# QUTMS_CMU_type2_1_1.net
KiCad netlist of a schematic drawn in Altium Designer
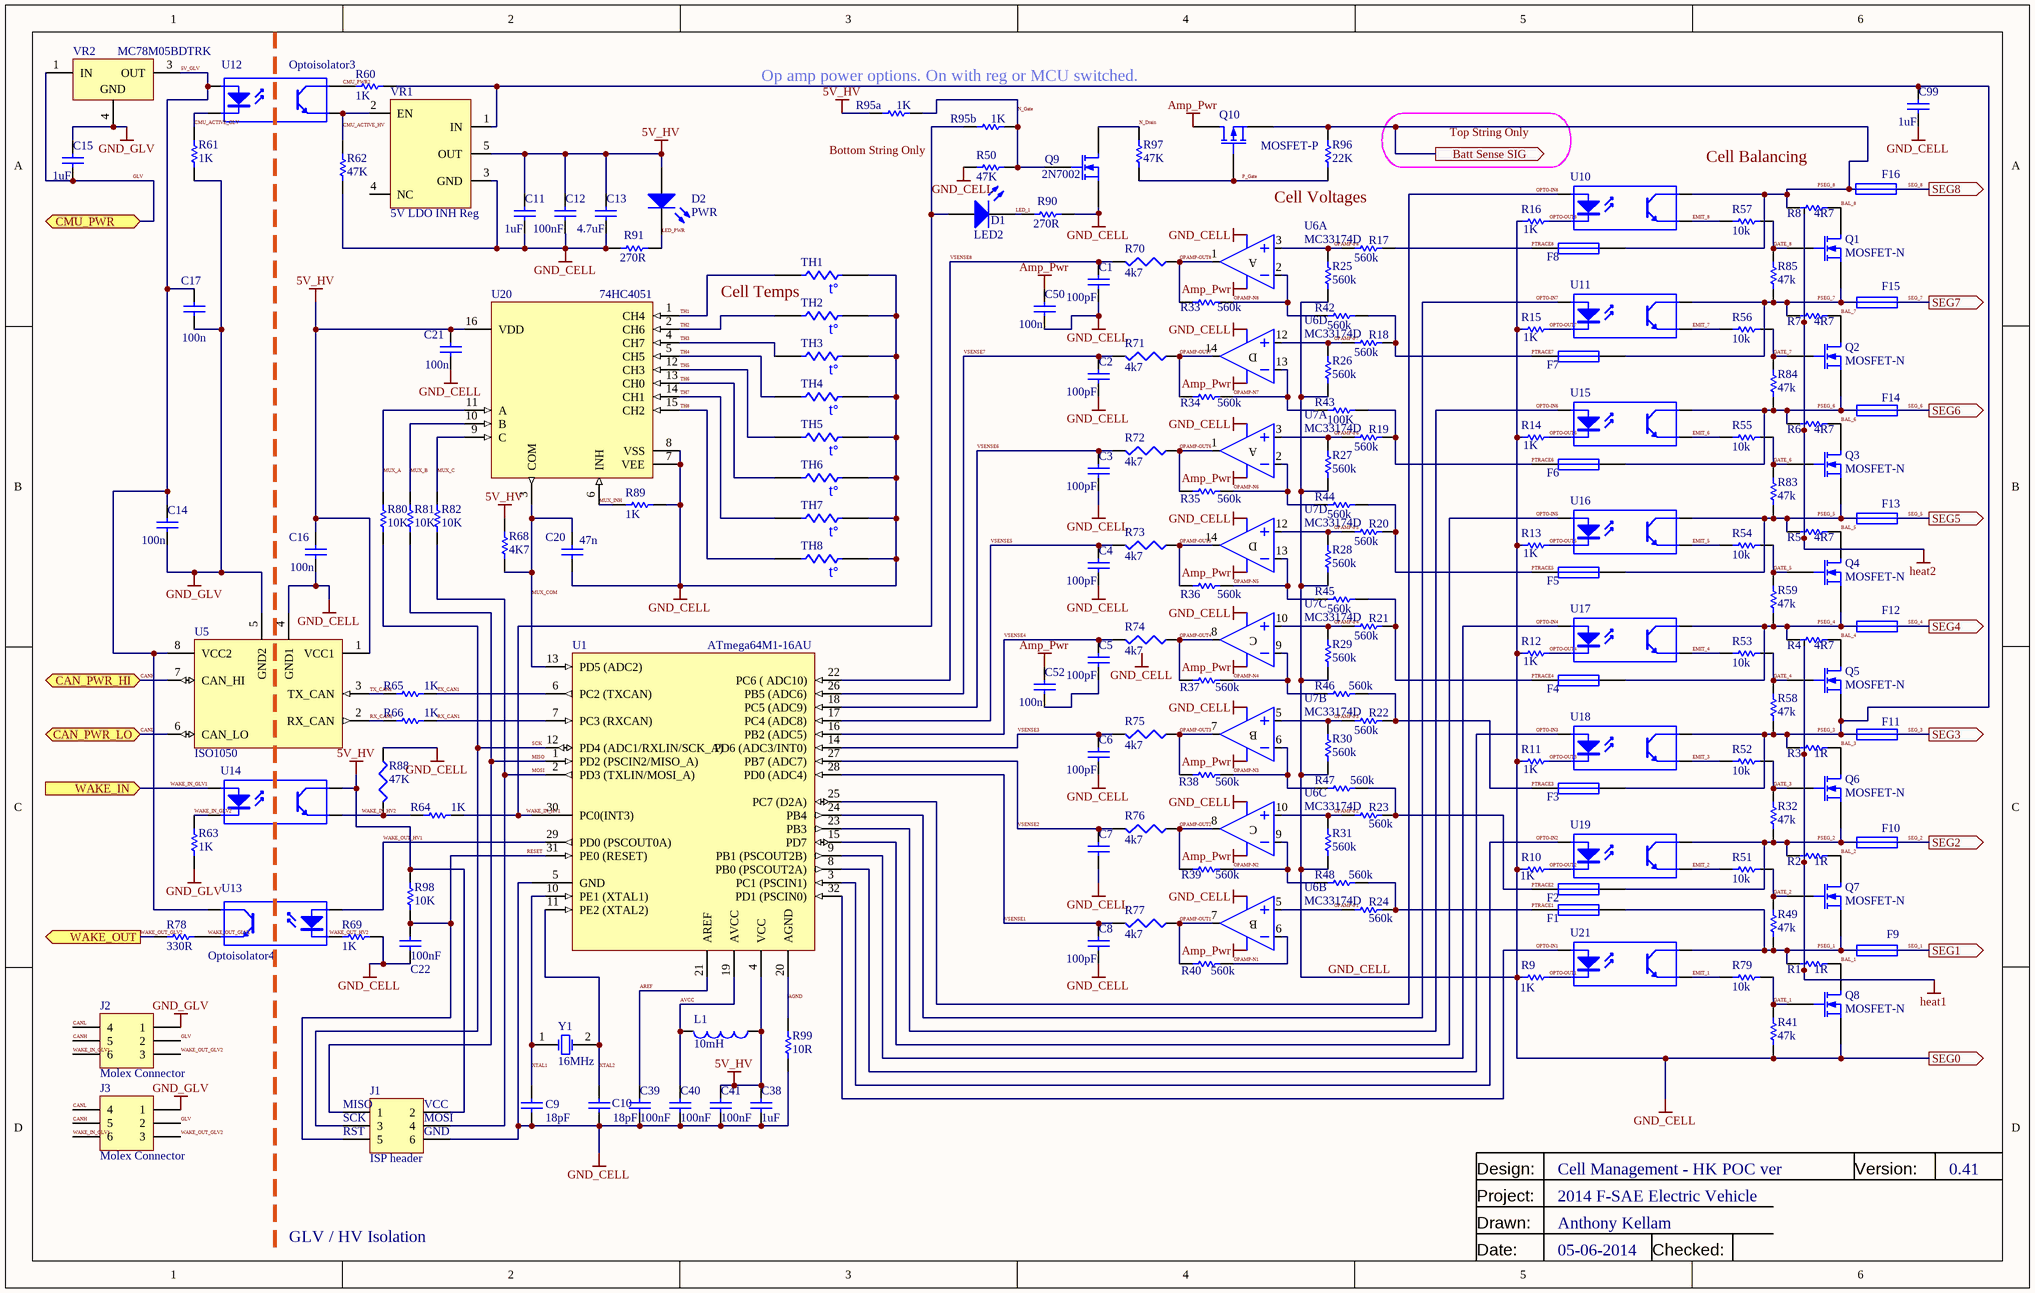
[diagram p0: QUTMS_CMU_type2_1_1.SchDoc]

(export (version "E")
  (design (tool "Eeschema 10.0.6"))
  (components
    (comp (ref "C1")
      (value "100pF")
      (footprint "1608[0603]")
      (description "0603")
      (fields
        (field (name "MANUFACTURER") "Samsung Electro-Mechanics America, Inc.")
        (field (name "MANUFACTURER PART NUMBER") "CL10B101KB8NNNC")
        (field (name "PUBLISHER") "Altium Limited")
      )
      (libsource (lib "Miscellaneous Devices") (part "Cap Semi"))
    )
    (comp (ref "C2")
      (value "100pF")
      (footprint "1608[0603]")
      (description "0603")
      (fields
        (field (name "MANUFACTURER") "Samsung Electro-Mechanics America, Inc.")
        (field (name "MANUFACTURER PART NUMBER") "CL10B101KB8NNNC")
        (field (name "PUBLISHER") "Altium Limited")
      )
      (libsource (lib "Miscellaneous Devices") (part "Cap Semi"))
    )
    (comp (ref "C3")
      (value "100pF")
      (footprint "1608[0603]")
      (description "0603")
      (fields
        (field (name "MANUFACTURER") "Samsung Electro-Mechanics America, Inc.")
        (field (name "MANUFACTURER PART NUMBER") "CL10B101KB8NNNC")
        (field (name "PUBLISHER") "Altium Limited")
      )
      (libsource (lib "Miscellaneous Devices") (part "Cap Semi"))
    )
    (comp (ref "C4")
      (value "100pF")
      (footprint "1608[0603]")
      (description "0603")
      (fields
        (field (name "MANUFACTURER") "Samsung Electro-Mechanics America, Inc.")
        (field (name "MANUFACTURER PART NUMBER") "CL10B101KB8NNNC")
        (field (name "PUBLISHER") "Altium Limited")
      )
      (libsource (lib "Miscellaneous Devices") (part "Cap Semi"))
    )
    (comp (ref "C5")
      (value "100pF")
      (footprint "1608[0603]")
      (description "0603")
      (fields
        (field (name "MANUFACTURER") "Samsung Electro-Mechanics America, Inc.")
        (field (name "MANUFACTURER PART NUMBER") "CL10B101KB8NNNC")
        (field (name "PUBLISHER") "Altium Limited")
      )
      (libsource (lib "Miscellaneous Devices") (part "Cap Semi"))
    )
    (comp (ref "C6")
      (value "100pF")
      (footprint "1608[0603]")
      (description "0603")
      (fields
        (field (name "MANUFACTURER") "Samsung Electro-Mechanics America, Inc.")
        (field (name "MANUFACTURER PART NUMBER") "CL10B101KB8NNNC")
        (field (name "PUBLISHER") "Altium Limited")
      )
      (libsource (lib "Miscellaneous Devices") (part "Cap Semi"))
    )
    (comp (ref "C7")
      (value "100pF")
      (footprint "1608[0603]")
      (description "0603")
      (fields
        (field (name "MANUFACTURER") "Samsung Electro-Mechanics America, Inc.")
        (field (name "MANUFACTURER PART NUMBER") "CL10B101KB8NNNC")
        (field (name "PUBLISHER") "Altium Limited")
      )
      (libsource (lib "Miscellaneous Devices") (part "Cap Semi"))
    )
    (comp (ref "C8")
      (value "100pF")
      (footprint "1608[0603]")
      (description "0603")
      (fields
        (field (name "MANUFACTURER") "Samsung Electro-Mechanics America, Inc.")
        (field (name "MANUFACTURER PART NUMBER") "CL10B101KB8NNNC")
        (field (name "PUBLISHER") "Altium Limited")
      )
      (libsource (lib "Miscellaneous Devices") (part "Cap Semi"))
    )
    (comp (ref "C9")
      (value "18pF")
      (footprint "1608[0603]")
      (description "0603")
      (fields (field (name "PUBLISHER") "Altium Limited"))
      (libsource (lib "Miscellaneous Devices") (part "Cap Semi"))
    )
    (comp (ref "C10")
      (value "18pF")
      (footprint "1608[0603]")
      (description "0603")
      (fields (field (name "PUBLISHER") "Altium Limited"))
      (libsource (lib "Miscellaneous Devices") (part "Cap Semi"))
    )
    (comp (ref "C11")
      (value "1uF")
      (footprint "1608[0603]")
      (description "0603")
      (fields (field (name "PUBLISHER") "Altium Limited"))
      (libsource (lib "Miscellaneous Devices") (part "Cap Semi"))
    )
    (comp (ref "C12")
      (value "100nF")
      (footprint "1608[0603]")
      (description "0603")
      (fields
        (field (name "MANUFACTURER") "Samsung Electro-Mechanics America, Inc.")
        (field (name "MANUFACTURER PART NUMBER") "CL10B104KB8SFNC")
        (field (name "PUBLISHER") "Altium Limited")
      )
      (libsource (lib "Miscellaneous Devices") (part "Cap Semi"))
    )
    (comp (ref "C13")
      (value "4.7uF")
      (footprint "1608[0603]")
      (description "0603")
      (fields (field (name "PUBLISHER") "Altium Limited"))
      (libsource (lib "Miscellaneous Devices") (part "Cap Semi"))
    )
    (comp (ref "C14")
      (value "100n")
      (footprint "1608[0603]")
      (description "0603")
      (fields
        (field (name "MANUFACTURER") "Samsung Electro-Mechanics America, Inc.")
        (field (name "MANUFACTURER PART NUMBER") "CL10B104KB8SFNC")
        (field (name "PUBLISHER") "Altium Limited")
      )
      (libsource (lib "Miscellaneous Devices") (part "Cap Semi"))
    )
    (comp (ref "C15")
      (value "1uF")
      (footprint "1608[0603]")
      (fields (field (name "Comment") "0603") (field (name "PUBLISHER") "Altium Limited"))
      (libsource (lib "Miscellaneous Devices") (part "Cap Semi"))
    )
    (comp (ref "C16")
      (value "100n")
      (footprint "1608[0603]")
      (description "0603")
      (fields
        (field (name "MANUFACTURER") "Samsung Electro-Mechanics America, Inc.")
        (field (name "MANUFACTURER PART NUMBER") "CL10B104KB8SFNC")
        (field (name "PUBLISHER") "Altium Limited")
      )
      (libsource (lib "Miscellaneous Devices") (part "Cap Semi"))
    )
    (comp (ref "C17")
      (value "100n")
      (footprint "1608[0603]")
      (description "0603")
      (fields
        (field (name "MANUFACTURER") "Samsung Electro-Mechanics America, Inc.")
        (field (name "MANUFACTURER PART NUMBER") "CL10B104KB8SFNC")
        (field (name "PUBLISHER") "Altium Limited")
      )
      (libsource (lib "Miscellaneous Devices") (part "Cap Semi"))
    )
    (comp (ref "C20")
      (value "47n")
      (footprint "1608[0603]")
      (description "47nF")
      (fields (field (name "Comment") "0603") (field (name "PUBLISHER") "Altium Limited"))
      (libsource (lib "Miscellaneous Devices") (part "Cap Semi"))
    )
    (comp (ref "C21")
      (value "100n")
      (footprint "1608[0603]")
      (description "0603")
      (fields
        (field (name "MANUFACTURER") "Samsung Electro-Mechanics America, Inc.")
        (field (name "MANUFACTURER PART NUMBER") "CL10B104KB8SFNC")
        (field (name "PUBLISHER") "Altium Limited")
      )
      (libsource (lib "Miscellaneous Devices") (part "Cap Semi"))
    )
    (comp (ref "C22")
      (value "100nF")
      (footprint "1608[0603]")
      (description "0603")
      (fields
        (field (name "MANUFACTURER") "Samsung Electro-Mechanics America, Inc.")
        (field (name "MANUFACTURER PART NUMBER") "CL10B104KB8SFNC")
        (field (name "PUBLISHER") "Altium Limited")
      )
      (libsource (lib "Miscellaneous Devices") (part "Cap Semi"))
    )
    (comp (ref "C38")
      (value "1uF")
      (footprint "1608[0603]")
      (description "0603")
      (fields (field (name "PUBLISHER") "Altium Limited"))
      (libsource (lib "Miscellaneous Devices") (part "Cap Semi"))
    )
    (comp (ref "C39")
      (value "100nF")
      (footprint "1608[0603]")
      (description "0603")
      (fields
        (field (name "MANUFACTURER") "Samsung Electro-Mechanics America, Inc.")
        (field (name "MANUFACTURER PART NUMBER") "CL10B104KB8SFNC")
        (field (name "PUBLISHER") "Altium Limited")
      )
      (libsource (lib "Miscellaneous Devices") (part "Cap Semi"))
    )
    (comp (ref "C40")
      (value "100nF")
      (footprint "1608[0603]")
      (description "0603")
      (fields
        (field (name "MANUFACTURER") "Samsung Electro-Mechanics America, Inc.")
        (field (name "MANUFACTURER PART NUMBER") "CL10B104KB8SFNC")
        (field (name "PUBLISHER") "Altium Limited")
      )
      (libsource (lib "Miscellaneous Devices") (part "Cap Semi"))
    )
    (comp (ref "C41")
      (value "100nF")
      (footprint "1608[0603]")
      (description "0603")
      (fields
        (field (name "MANUFACTURER") "Samsung Electro-Mechanics America, Inc.")
        (field (name "MANUFACTURER PART NUMBER") "CL10B104KB8SFNC")
        (field (name "PUBLISHER") "Altium Limited")
      )
      (libsource (lib "Miscellaneous Devices") (part "Cap Semi"))
    )
    (comp (ref "C50")
      (value "100n")
      (footprint "1608[0603]")
      (description "0603")
      (fields
        (field (name "MANUFACTURER") "Samsung Electro-Mechanics America, Inc.")
        (field (name "MANUFACTURER PART NUMBER") "CL10B104KB8SFNC")
        (field (name "PUBLISHER") "Altium Limited")
      )
      (libsource (lib "Miscellaneous Devices") (part "Cap Semi"))
    )
    (comp (ref "C52")
      (value "100n")
      (footprint "1608[0603]")
      (description "0603")
      (fields
        (field (name "MANUFACTURER") "Samsung Electro-Mechanics America, Inc.")
        (field (name "MANUFACTURER PART NUMBER") "CL10B104KB8SFNC")
        (field (name "PUBLISHER") "Altium Limited")
      )
      (libsource (lib "Miscellaneous Devices") (part "Cap Semi"))
    )
    (comp (ref "C99")
      (value "1uF")
      (footprint "1608[0603]")
      (description "0603")
      (fields (field (name "PUBLISHER") "Altium Limited"))
      (libsource (lib "Miscellaneous Devices") (part "Cap Semi"))
    )
    (comp (ref "D1")
      (value "LED2")
      (footprint "2012[0805]_Res")
      (description "Typical RED, GREEN, YELLOW, AMBER GaAs LED")
      (fields
        (field (name "MANUFACTURER") "Kingbright")
        (field (name "MANUFACTURER PART NUMBER") "APT2012SGC")
        (field (name "PUBLISHER") "Altium Limited")
      )
      (libsource (lib "Miscellaneous Devices") (part "LED2"))
    )
    (comp (ref "D2")
      (value "PWR")
      (footprint "2012[0805]_Res")
      (description "Typical RED, GREEN, YELLOW, AMBER GaAs LED")
      (fields
        (field (name "MANUFACTURER") "OSRAM Opto Semiconductors Inc.")
        (field (name "MANUFACTURER PART NUMBER") "LS R976-NR-1")
        (field (name "PUBLISHER") "Altium Limited")
      )
      (libsource (lib "Miscellaneous Devices") (part "LED2"))
    )
    (comp (ref "F1")
      (value "Fuse 1")
      (footprint "3216[1206]")
      (description "Fuse")
      (fields
        (field (name "MANUFACTURER") "Schurter Inc.")
        (field (name "MANUFACTURER PART NUMBER") "3413.0008.22")
        (field (name "PUBLISHER") "Altium Limited")
      )
      (libsource (lib "Miscellaneous Devices") (part "Fuse 1"))
    )
    (comp (ref "F2")
      (value "Fuse 1")
      (footprint "3216[1206]")
      (description "Fuse")
      (fields
        (field (name "MANUFACTURER") "Schurter Inc.")
        (field (name "MANUFACTURER PART NUMBER") "3413.0008.22")
        (field (name "PUBLISHER") "Altium Limited")
      )
      (libsource (lib "Miscellaneous Devices") (part "Fuse 1"))
    )
    (comp (ref "F3")
      (value "Fuse 1")
      (footprint "3216[1206]")
      (description "Fuse")
      (fields
        (field (name "MANUFACTURER") "Schurter Inc.")
        (field (name "MANUFACTURER PART NUMBER") "3413.0008.22")
        (field (name "PUBLISHER") "Altium Limited")
      )
      (libsource (lib "Miscellaneous Devices") (part "Fuse 1"))
    )
    (comp (ref "F4")
      (value "Fuse 1")
      (footprint "3216[1206]")
      (description "Fuse")
      (fields
        (field (name "MANUFACTURER") "Schurter Inc.")
        (field (name "MANUFACTURER PART NUMBER") "3413.0008.22")
        (field (name "PUBLISHER") "Altium Limited")
      )
      (libsource (lib "Miscellaneous Devices") (part "Fuse 1"))
    )
    (comp (ref "F5")
      (value "Fuse 1")
      (footprint "3216[1206]")
      (description "Fuse")
      (fields
        (field (name "MANUFACTURER") "Schurter Inc.")
        (field (name "MANUFACTURER PART NUMBER") "3413.0008.22")
        (field (name "PUBLISHER") "Altium Limited")
      )
      (libsource (lib "Miscellaneous Devices") (part "Fuse 1"))
    )
    (comp (ref "F6")
      (value "Fuse 1")
      (footprint "3216[1206]")
      (description "Fuse")
      (fields
        (field (name "MANUFACTURER") "Schurter Inc.")
        (field (name "MANUFACTURER PART NUMBER") "3413.0008.22")
        (field (name "PUBLISHER") "Altium Limited")
      )
      (libsource (lib "Miscellaneous Devices") (part "Fuse 1"))
    )
    (comp (ref "F7")
      (value "Fuse 1")
      (footprint "3216[1206]")
      (description "Fuse")
      (fields
        (field (name "MANUFACTURER") "Schurter Inc.")
        (field (name "MANUFACTURER PART NUMBER") "3413.0008.22")
        (field (name "PUBLISHER") "Altium Limited")
      )
      (libsource (lib "Miscellaneous Devices") (part "Fuse 1"))
    )
    (comp (ref "F8")
      (value "Fuse 1")
      (footprint "3216[1206]")
      (description "Fuse")
      (fields
        (field (name "MANUFACTURER") "Schurter Inc.")
        (field (name "MANUFACTURER PART NUMBER") "3413.0008.22")
        (field (name "PUBLISHER") "Altium Limited")
      )
      (libsource (lib "Miscellaneous Devices") (part "Fuse 1"))
    )
    (comp (ref "F9")
      (value "Fuse 1")
      (footprint "FootprintLibrary:6426[2410]_Fuse")
      (description "Fuse")
      (fields
        (field (name "MANUFACTURER") "Bel Fuse Inc.")
        (field (name "MANUFACTURER PART NUMBER") "0679L5000-05")
        (field (name "PUBLISHER") "Altium Limited")
      )
      (libsource (lib "") (part "Fuse 1_1"))
    )
    (comp (ref "F10")
      (value "Fuse 1")
      (footprint "6426[2410]_Fuse")
      (description "Fuse")
      (fields
        (field (name "MANUFACTURER") "Bel Fuse Inc.")
        (field (name "MANUFACTURER PART NUMBER") "0679L5000-05")
        (field (name "PUBLISHER") "Altium Limited")
      )
      (libsource (lib "") (part "Fuse 1_1"))
    )
    (comp (ref "F11")
      (value "Fuse 1")
      (footprint "6426[2410]_Fuse")
      (description "Fuse")
      (fields
        (field (name "MANUFACTURER") "Bel Fuse Inc.")
        (field (name "MANUFACTURER PART NUMBER") "0679L5000-05")
        (field (name "PUBLISHER") "Altium Limited")
      )
      (libsource (lib "") (part "Fuse 1_1"))
    )
    (comp (ref "F12")
      (value "Fuse 1")
      (footprint "6426[2410]_Fuse")
      (description "Fuse")
      (fields
        (field (name "MANUFACTURER") "Bel Fuse Inc.")
        (field (name "MANUFACTURER PART NUMBER") "0679L5000-05")
        (field (name "PUBLISHER") "Altium Limited")
      )
      (libsource (lib "") (part "Fuse 1_1"))
    )
    (comp (ref "F13")
      (value "Fuse 1")
      (footprint "6426[2410]_Fuse")
      (description "Fuse")
      (fields
        (field (name "MANUFACTURER") "Bel Fuse Inc.")
        (field (name "MANUFACTURER PART NUMBER") "0679L5000-05")
        (field (name "PUBLISHER") "Altium Limited")
      )
      (libsource (lib "") (part "Fuse 1_1"))
    )
    (comp (ref "F14")
      (value "Fuse 1")
      (footprint "6426[2410]_Fuse")
      (description "Fuse")
      (fields
        (field (name "MANUFACTURER") "Bel Fuse Inc.")
        (field (name "MANUFACTURER PART NUMBER") "0679L5000-05")
        (field (name "PUBLISHER") "Altium Limited")
      )
      (libsource (lib "") (part "Fuse 1_1"))
    )
    (comp (ref "F15")
      (value "Fuse 1")
      (footprint "6426[2410]_Fuse")
      (description "Fuse")
      (fields
        (field (name "MANUFACTURER") "Bel Fuse Inc.")
        (field (name "MANUFACTURER PART NUMBER") "0679L5000-05")
        (field (name "PUBLISHER") "Altium Limited")
      )
      (libsource (lib "") (part "Fuse 1_1"))
    )
    (comp (ref "F16")
      (value "Fuse 1")
      (footprint "6426[2410]_Fuse")
      (description "Fuse")
      (fields
        (field (name "MANUFACTURER") "Bel Fuse Inc.")
        (field (name "MANUFACTURER PART NUMBER") "0679L5000-05")
        (field (name "PUBLISHER") "Altium Limited")
      )
      (libsource (lib "") (part "Fuse 1_1"))
    )
    (comp (ref "J1")
      (value "ISP header")
      (footprint "ISP Header")
      (description "Header, 3-Pin, Dual row")
      (fields
        (field (name "MANUFACTURER") "Amphenol FCI")
        (field (name "MANUFACTURER PART NUMBER") "95278-101A06LF")
        (field (name "PUBLISHER") "Altium Limited")
      )
      (libsource (lib "Miscellaneous Connectors") (part "Header 3X2"))
    )
    (comp (ref "J2")
      (value "Molex Connector")
      (footprint "MOLEX_6H_2")
      (description "Header, 3-Pin, Dual row")
      (fields
        (field (name "MANUFACTURER") "Molex, LLC")
        (field (name "MANUFACTURER PART NUMBER") "0430450610")
        (field (name "PUBLISHER") "Altium Limited")
      )
      (libsource (lib "Miscellaneous Connectors") (part "Header 3X2A"))
    )
    (comp (ref "J3")
      (value "Molex Connector")
      (footprint "MOLEX_6H_1")
      (description "Header, 3-Pin, Dual row")
      (fields
        (field (name "MANUFACTURER") "Molex, LLC")
        (field (name "MANUFACTURER PART NUMBER") "0430450610")
        (field (name "PUBLISHER") "Altium Limited")
      )
      (libsource (lib "Miscellaneous Connectors") (part "Header 3X2A"))
    )
    (comp (ref "L1")
      (value "10mH")
      (footprint "2012[0805]_IND")
      (description "0805")
      (fields (field (name "Comment") "10uH") (field (name "PUBLISHER") "Altium Limited"))
      (libsource (lib "Miscellaneous Devices") (part "Inductor"))
    )
    (comp (ref "Q1")
      (value "MOSFET-N")
      (footprint "D2PAK_L")
      (description "N-Channel MOSFET")
      (fields
        (field (name "MANUFACTURER") "Fairchild Semiconductor")
        (field (name "MANUFACTURER PART NUMBER") "FDD86250")
        (field (name "PUBLISHER") "Altium Limited")
      )
      (libsource (lib "") (part "MOSFET-N_1"))
    )
    (comp (ref "Q2")
      (value "MOSFET-N")
      (footprint "D2PAK_L")
      (description "N-Channel MOSFET")
      (fields
        (field (name "MANUFACTURER") "Fairchild Semiconductor")
        (field (name "MANUFACTURER PART NUMBER") "FDD86250")
        (field (name "PUBLISHER") "Altium Limited")
      )
      (libsource (lib "") (part "MOSFET-N_1"))
    )
    (comp (ref "Q3")
      (value "MOSFET-N")
      (footprint "D2PAK_L")
      (description "N-Channel MOSFET")
      (fields
        (field (name "MANUFACTURER") "Fairchild Semiconductor")
        (field (name "MANUFACTURER PART NUMBER") "FDD86250")
        (field (name "PUBLISHER") "Altium Limited")
      )
      (libsource (lib "") (part "MOSFET-N_1"))
    )
    (comp (ref "Q4")
      (value "MOSFET-N")
      (footprint "D2PAK_L")
      (description "N-Channel MOSFET")
      (fields
        (field (name "MANUFACTURER") "Fairchild Semiconductor")
        (field (name "MANUFACTURER PART NUMBER") "FDD86250")
        (field (name "PUBLISHER") "Altium Limited")
      )
      (libsource (lib "") (part "MOSFET-N_1"))
    )
    (comp (ref "Q5")
      (value "MOSFET-N")
      (footprint "D2PAK_L")
      (description "N-Channel MOSFET")
      (fields
        (field (name "MANUFACTURER") "Fairchild Semiconductor")
        (field (name "MANUFACTURER PART NUMBER") "FDD86250")
        (field (name "PUBLISHER") "Altium Limited")
      )
      (libsource (lib "") (part "MOSFET-N_1"))
    )
    (comp (ref "Q6")
      (value "MOSFET-N")
      (footprint "D2PAK_L")
      (description "N-Channel MOSFET")
      (fields
        (field (name "MANUFACTURER") "Fairchild Semiconductor")
        (field (name "MANUFACTURER PART NUMBER") "FDD86250")
        (field (name "PUBLISHER") "Altium Limited")
      )
      (libsource (lib "") (part "MOSFET-N_1"))
    )
    (comp (ref "Q7")
      (value "MOSFET-N")
      (footprint "D2PAK_L")
      (description "N-Channel MOSFET")
      (fields
        (field (name "MANUFACTURER") "Fairchild Semiconductor")
        (field (name "MANUFACTURER PART NUMBER") "FDD86250")
        (field (name "PUBLISHER") "Altium Limited")
      )
      (libsource (lib "") (part "MOSFET-N_1"))
    )
    (comp (ref "Q8")
      (value "MOSFET-N")
      (footprint "D2PAK_L")
      (description "N-Channel MOSFET")
      (fields
        (field (name "MANUFACTURER") "Fairchild Semiconductor")
        (field (name "MANUFACTURER PART NUMBER") "FDD86250")
        (field (name "PUBLISHER") "Altium Limited")
      )
      (libsource (lib "") (part "MOSFET-N_1"))
    )
    (comp (ref "Q9")
      (value "2N7002")
      (footprint "SOT23_N")
      (description "N-Channel MOSFET")
      (fields
        (field (name "MANUFACTURER") "NXP Semiconductors")
        (field (name "MANUFACTURER PART NUMBER") "2N7002P,215")
        (field (name "PUBLISHER") "Altium Limited")
      )
      (libsource (lib "Miscellaneous Devices") (part "MOSFET-N"))
    )
    (comp (ref "Q10")
      (value "MOSFET-P")
      (footprint "SOT23_N")
      (description "P-Channel MOSFET")
      (fields
        (field (name "MANUFACTURER") "Vishay Siliconix")
        (field (name "MANUFACTURER PART NUMBER") "TP0610K-T1-GE3")
        (field (name "PUBLISHER") "Altium Limited")
      )
      (libsource (lib "Miscellaneous Devices") (part "MOSFET-P"))
    )
    (comp (ref "R1")
      (value "1R")
      (footprint "D2PAK_N")
      (description "Power Resistor SMD")
      (fields
        (field (name "MANUFACTURER") "Bourns Inc.")
        (field (name "MANUFACTURER PART NUMBER") "PWR163S-25-1R00J")
        (field (name "PUBLISHER") "Altium Limited")
      )
      (libsource (lib "") (part "Res1_1"))
    )
    (comp (ref "R2")
      (value "1R")
      (footprint "D2PAK_N")
      (description "Power Resistor SMD")
      (fields
        (field (name "MANUFACTURER") "Bourns Inc.")
        (field (name "MANUFACTURER PART NUMBER") "PWR163S-25-1R00J")
        (field (name "PUBLISHER") "Altium Limited")
      )
      (libsource (lib "") (part "Res1_1"))
    )
    (comp (ref "R3")
      (value "1R")
      (footprint "D2PAK_N")
      (description "Power Resistor SMD")
      (fields
        (field (name "MANUFACTURER") "Bourns Inc.")
        (field (name "MANUFACTURER PART NUMBER") "PWR163S-25-1R00J")
        (field (name "PUBLISHER") "Altium Limited")
      )
      (libsource (lib "") (part "Res1_1"))
    )
    (comp (ref "R4")
      (value "4R7")
      (footprint "D2PAK_N")
      (description "Power Resistor SMD")
      (fields
        (field (name "MANUFACTURER") "Bourns Inc.")
        (field (name "MANUFACTURER PART NUMBER") "PWR163S-25-1R00J")
        (field (name "PUBLISHER") "Altium Limited")
      )
      (libsource (lib "") (part "Res1_1"))
    )
    (comp (ref "R5")
      (value "4R7")
      (footprint "D2PAK_N")
      (description "Power Resistor SMD")
      (fields
        (field (name "MANUFACTURER") "Bourns Inc.")
        (field (name "MANUFACTURER PART NUMBER") "PWR163S-25-1R00J")
        (field (name "PUBLISHER") "Altium Limited")
      )
      (libsource (lib "") (part "Res1_1"))
    )
    (comp (ref "R6")
      (value "4R7")
      (footprint "D2PAK_N")
      (description "Power Resistor SMD")
      (fields
        (field (name "MANUFACTURER") "Bourns Inc.")
        (field (name "MANUFACTURER PART NUMBER") "PWR163S-25-1R00J")
        (field (name "PUBLISHER") "Altium Limited")
      )
      (libsource (lib "") (part "Res1_1"))
    )
    (comp (ref "R7")
      (value "4R7")
      (footprint "D2PAK_N")
      (description "Power Resistor SMD")
      (fields
        (field (name "MANUFACTURER") "Bourns Inc.")
        (field (name "MANUFACTURER PART NUMBER") "PWR163S-25-1R00J")
        (field (name "PUBLISHER") "Altium Limited")
      )
      (libsource (lib "") (part "Res1_1"))
    )
    (comp (ref "R8")
      (value "4R7")
      (footprint "D2PAK_N")
      (description "Power Resistor SMD")
      (fields
        (field (name "MANUFACTURER") "Bourns Inc.")
        (field (name "MANUFACTURER PART NUMBER") "PWR163S-25-1R00J")
        (field (name "PUBLISHER") "Altium Limited")
      )
      (libsource (lib "") (part "Res1_1"))
    )
    (comp (ref "R9")
      (value "1K")
      (footprint "2012[0805]_Res")
      (description "0805")
      (fields (field (name "Comment") "1k") (field (name "PUBLISHER") "Altium Limited"))
      (libsource (lib "Miscellaneous Devices") (part "Res1"))
    )
    (comp (ref "R10")
      (value "1K")
      (footprint "2012[0805]_Res")
      (description "0805")
      (fields (field (name "Comment") "1k") (field (name "PUBLISHER") "Altium Limited"))
      (libsource (lib "Miscellaneous Devices") (part "Res1"))
    )
    (comp (ref "R11")
      (value "1K")
      (footprint "2012[0805]_Res")
      (description "0805")
      (fields (field (name "Comment") "1k") (field (name "PUBLISHER") "Altium Limited"))
      (libsource (lib "Miscellaneous Devices") (part "Res1"))
    )
    (comp (ref "R12")
      (value "1K")
      (footprint "2012[0805]_Res")
      (description "0805")
      (fields (field (name "Comment") "1k") (field (name "PUBLISHER") "Altium Limited"))
      (libsource (lib "Miscellaneous Devices") (part "Res1"))
    )
    (comp (ref "R13")
      (value "1K")
      (footprint "2012[0805]_Res")
      (description "0805")
      (fields (field (name "Comment") "1k") (field (name "PUBLISHER") "Altium Limited"))
      (libsource (lib "Miscellaneous Devices") (part "Res1"))
    )
    (comp (ref "R14")
      (value "1K")
      (footprint "2012[0805]_Res")
      (description "0805")
      (fields (field (name "Comment") "1k") (field (name "PUBLISHER") "Altium Limited"))
      (libsource (lib "Miscellaneous Devices") (part "Res1"))
    )
    (comp (ref "R15")
      (value "1K")
      (footprint "2012[0805]_Res")
      (description "0805")
      (fields (field (name "Comment") "1k") (field (name "PUBLISHER") "Altium Limited"))
      (libsource (lib "Miscellaneous Devices") (part "Res1"))
    )
    (comp (ref "R16")
      (value "1K")
      (footprint "2012[0805]_Res")
      (description "0805")
      (fields (field (name "Comment") "1k") (field (name "PUBLISHER") "Altium Limited"))
      (libsource (lib "Miscellaneous Devices") (part "Res1"))
    )
    (comp (ref "R17")
      (value "560k")
      (footprint "2012[0805]_Res")
      (description "0805")
      (fields
        (field (name "MANUFACTURER") "Yageo")
        (field (name "MANUFACTURER PART NUMBER") "RC0805JR-07560KL")
        (field (name "PUBLISHER") "Altium Limited")
      )
      (libsource (lib "") (part "Res1_2"))
    )
    (comp (ref "R18")
      (value "560k")
      (footprint "2012[0805]_Res")
      (description "0805")
      (fields
        (field (name "MANUFACTURER") "Yageo")
        (field (name "MANUFACTURER PART NUMBER") "RC0805JR-07560KL")
        (field (name "PUBLISHER") "Altium Limited")
      )
      (libsource (lib "") (part "Res1_2"))
    )
    (comp (ref "R19")
      (value "560k")
      (footprint "2012[0805]_Res")
      (description "0805")
      (fields
        (field (name "MANUFACTURER") "Yageo")
        (field (name "MANUFACTURER PART NUMBER") "RC0805JR-07560KL")
        (field (name "PUBLISHER") "Altium Limited")
      )
      (libsource (lib "") (part "Res1_2"))
    )
    (comp (ref "R20")
      (value "560k")
      (footprint "2012[0805]_Res")
      (description "0805")
      (fields
        (field (name "MANUFACTURER") "Yageo")
        (field (name "MANUFACTURER PART NUMBER") "RC0805JR-07560KL")
        (field (name "PUBLISHER") "Altium Limited")
      )
      (libsource (lib "") (part "Res1_2"))
    )
    (comp (ref "R21")
      (value "560k")
      (footprint "2012[0805]_Res")
      (description "0805")
      (fields
        (field (name "MANUFACTURER") "Yageo")
        (field (name "MANUFACTURER PART NUMBER") "RC0805JR-07560KL")
        (field (name "PUBLISHER") "Altium Limited")
      )
      (libsource (lib "") (part "Res1_2"))
    )
    (comp (ref "R22")
      (value "560k")
      (footprint "2012[0805]_Res")
      (description "0805")
      (fields
        (field (name "MANUFACTURER") "Yageo")
        (field (name "MANUFACTURER PART NUMBER") "RC0805JR-07560KL")
        (field (name "PUBLISHER") "Altium Limited")
      )
      (libsource (lib "") (part "Res1_2"))
    )
    (comp (ref "R23")
      (value "560k")
      (footprint "2012[0805]_Res")
      (description "0805")
      (fields
        (field (name "MANUFACTURER") "Yageo")
        (field (name "MANUFACTURER PART NUMBER") "RC0805JR-07560KL")
        (field (name "PUBLISHER") "Altium Limited")
      )
      (libsource (lib "") (part "Res1_2"))
    )
    (comp (ref "R24")
      (value "560k")
      (footprint "2012[0805]_Res")
      (description "0805")
      (fields
        (field (name "MANUFACTURER") "Yageo")
        (field (name "MANUFACTURER PART NUMBER") "RC0805JR-07560KL")
        (field (name "PUBLISHER") "Altium Limited")
      )
      (libsource (lib "") (part "Res1_2"))
    )
    (comp (ref "R25")
      (value "560k")
      (footprint "2012[0805]_Res")
      (description "0805")
      (fields
        (field (name "MANUFACTURER") "Yageo")
        (field (name "MANUFACTURER PART NUMBER") "RC0805JR-07560KL")
        (field (name "PUBLISHER") "Altium Limited")
      )
      (libsource (lib "") (part "Res1_2"))
    )
    (comp (ref "R26")
      (value "560k")
      (footprint "2012[0805]_Res")
      (description "0805")
      (fields
        (field (name "MANUFACTURER") "Yageo")
        (field (name "MANUFACTURER PART NUMBER") "RC0805JR-07560KL")
        (field (name "PUBLISHER") "Altium Limited")
      )
      (libsource (lib "") (part "Res1_2"))
    )
    (comp (ref "R27")
      (value "560k")
      (footprint "2012[0805]_Res")
      (description "0805")
      (fields
        (field (name "MANUFACTURER") "Yageo")
        (field (name "MANUFACTURER PART NUMBER") "RC0805JR-07560KL")
        (field (name "PUBLISHER") "Altium Limited")
      )
      (libsource (lib "") (part "Res1_2"))
    )
    (comp (ref "R28")
      (value "560k")
      (footprint "2012[0805]_Res")
      (description "0805")
      (fields
        (field (name "MANUFACTURER") "Yageo")
        (field (name "MANUFACTURER PART NUMBER") "RC0805JR-07560KL")
        (field (name "PUBLISHER") "Altium Limited")
      )
      (libsource (lib "") (part "Res1_2"))
    )
    (comp (ref "R29")
      (value "560k")
      (footprint "2012[0805]_Res")
      (description "0805")
      (fields
        (field (name "MANUFACTURER") "Yageo")
        (field (name "MANUFACTURER PART NUMBER") "RC0805JR-07560KL")
        (field (name "PUBLISHER") "Altium Limited")
      )
      (libsource (lib "") (part "Res1_2"))
    )
    (comp (ref "R30")
      (value "560k")
      (footprint "2012[0805]_Res")
      (description "0805")
      (fields
        (field (name "MANUFACTURER") "Yageo")
        (field (name "MANUFACTURER PART NUMBER") "RC0805JR-07560KL")
        (field (name "PUBLISHER") "Altium Limited")
      )
      (libsource (lib "") (part "Res1_2"))
    )
    (comp (ref "R31")
      (value "560k")
      (footprint "2012[0805]_Res")
      (description "0805")
      (fields
        (field (name "MANUFACTURER") "Yageo")
        (field (name "MANUFACTURER PART NUMBER") "RC0805JR-07560KL")
        (field (name "PUBLISHER") "Altium Limited")
      )
      (libsource (lib "") (part "Res1_2"))
    )
    (comp (ref "R32")
      (value "47k")
      (footprint "2012[0805]_Res")
      (description "0805")
      (fields
        (field (name "MANUFACTURER") "Panasonic Electronic Components")
        (field (name "MANUFACTURER PART NUMBER") "ERJ-6GEYJ473V")
        (field (name "PUBLISHER") "Altium Limited")
      )
      (libsource (lib "") (part "Res1_2"))
    )
    (comp (ref "R33")
      (value "560k")
      (footprint "2012[0805]_Res")
      (description "0805")
      (fields
        (field (name "MANUFACTURER") "Yageo")
        (field (name "MANUFACTURER PART NUMBER") "RC0805JR-07560KL")
        (field (name "PUBLISHER") "Altium Limited")
      )
      (libsource (lib "") (part "Res1_2"))
    )
    (comp (ref "R34")
      (value "560k")
      (footprint "2012[0805]_Res")
      (description "0805")
      (fields
        (field (name "MANUFACTURER") "Yageo")
        (field (name "MANUFACTURER PART NUMBER") "RC0805JR-07560KL")
        (field (name "PUBLISHER") "Altium Limited")
      )
      (libsource (lib "") (part "Res1_2"))
    )
    (comp (ref "R35")
      (value "560k")
      (footprint "2012[0805]_Res")
      (description "0805")
      (fields
        (field (name "MANUFACTURER") "Yageo")
        (field (name "MANUFACTURER PART NUMBER") "RC0805JR-07560KL")
        (field (name "PUBLISHER") "Altium Limited")
      )
      (libsource (lib "") (part "Res1_2"))
    )
    (comp (ref "R36")
      (value "560k")
      (footprint "2012[0805]_Res")
      (description "0805")
      (fields
        (field (name "MANUFACTURER") "Yageo")
        (field (name "MANUFACTURER PART NUMBER") "RC0805JR-07560KL")
        (field (name "PUBLISHER") "Altium Limited")
      )
      (libsource (lib "") (part "Res1_2"))
    )
    (comp (ref "R37")
      (value "560k")
      (footprint "2012[0805]_Res")
      (description "0805")
      (fields
        (field (name "MANUFACTURER") "Yageo")
        (field (name "MANUFACTURER PART NUMBER") "RC0805JR-07560KL")
        (field (name "PUBLISHER") "Altium Limited")
      )
      (libsource (lib "") (part "Res1_2"))
    )
    (comp (ref "R38")
      (value "560k")
      (footprint "2012[0805]_Res")
      (description "0805")
      (fields
        (field (name "MANUFACTURER") "Yageo")
        (field (name "MANUFACTURER PART NUMBER") "RC0805JR-07560KL")
        (field (name "PUBLISHER") "Altium Limited")
      )
      (libsource (lib "") (part "Res1_2"))
    )
    (comp (ref "R39")
      (value "560k")
      (footprint "2012[0805]_Res")
      (description "0805")
      (fields
        (field (name "MANUFACTURER") "Yageo")
        (field (name "MANUFACTURER PART NUMBER") "RC0805JR-07560KL")
        (field (name "PUBLISHER") "Altium Limited")
      )
      (libsource (lib "") (part "Res1_2"))
    )
    (comp (ref "R40")
      (value "560k")
      (footprint "2012[0805]_Res")
      (description "0805")
      (fields
        (field (name "MANUFACTURER") "Yageo")
        (field (name "MANUFACTURER PART NUMBER") "RC0805JR-07560KL")
        (field (name "PUBLISHER") "Altium Limited")
      )
      (libsource (lib "") (part "Res1_2"))
    )
    (comp (ref "R41")
      (value "47k")
      (footprint "2012[0805]_Res")
      (description "0805")
      (fields
        (field (name "MANUFACTURER") "Panasonic Electronic Components")
        (field (name "MANUFACTURER PART NUMBER") "ERJ-6GEYJ473V")
        (field (name "PUBLISHER") "Altium Limited")
      )
      (libsource (lib "") (part "Res1_2"))
    )
    (comp (ref "R42")
      (value "560k")
      (footprint "2012[0805]_Res")
      (description "0805")
      (fields
        (field (name "MANUFACTURER") "Yageo")
        (field (name "MANUFACTURER PART NUMBER") "RC0805JR-07560KL")
        (field (name "PUBLISHER") "Altium Limited")
      )
      (libsource (lib "") (part "Res1_2"))
    )
    (comp (ref "R43")
      (value "100K")
      (footprint "2012[0805]_Res")
      (description "0805")
      (fields
        (field (name "MANUFACTURER") "Yageo")
        (field (name "MANUFACTURER PART NUMBER") "RC0805JR-07560KL")
        (field (name "PUBLISHER") "Altium Limited")
      )
      (libsource (lib "") (part "Res1_2"))
    )
    (comp (ref "R44")
      (value "560k")
      (footprint "2012[0805]_Res")
      (description "0805")
      (fields
        (field (name "MANUFACTURER") "Yageo")
        (field (name "MANUFACTURER PART NUMBER") "RC0805JR-07560KL")
        (field (name "PUBLISHER") "Altium Limited")
      )
      (libsource (lib "") (part "Res1_2"))
    )
    (comp (ref "R45")
      (value "560k")
      (footprint "2012[0805]_Res")
      (description "0805")
      (fields
        (field (name "MANUFACTURER") "Yageo")
        (field (name "MANUFACTURER PART NUMBER") "RC0805JR-07560KL")
        (field (name "PUBLISHER") "Altium Limited")
      )
      (libsource (lib "") (part "Res1_2"))
    )
    (comp (ref "R46")
      (value "560k")
      (footprint "2012[0805]_Res")
      (description "0805")
      (fields
        (field (name "MANUFACTURER") "Yageo")
        (field (name "MANUFACTURER PART NUMBER") "RC0805JR-07560KL")
        (field (name "PUBLISHER") "Altium Limited")
      )
      (libsource (lib "") (part "Res1_2"))
    )
    (comp (ref "R47")
      (value "560k")
      (footprint "2012[0805]_Res")
      (description "0805")
      (fields
        (field (name "MANUFACTURER") "Yageo")
        (field (name "MANUFACTURER PART NUMBER") "RC0805JR-07560KL")
        (field (name "PUBLISHER") "Altium Limited")
      )
      (libsource (lib "") (part "Res1_2"))
    )
    (comp (ref "R48")
      (value "560k")
      (footprint "2012[0805]_Res")
      (description "0805")
      (fields
        (field (name "MANUFACTURER") "Yageo")
        (field (name "MANUFACTURER PART NUMBER") "RC0805JR-07560KL")
        (field (name "PUBLISHER") "Altium Limited")
      )
      (libsource (lib "") (part "Res1_2"))
    )
    (comp (ref "R49")
      (value "47k")
      (footprint "2012[0805]_Res")
      (description "0805")
      (fields
        (field (name "MANUFACTURER") "Panasonic Electronic Components")
        (field (name "MANUFACTURER PART NUMBER") "ERJ-6GEYJ473V")
        (field (name "PUBLISHER") "Altium Limited")
      )
      (libsource (lib "") (part "Res1_2"))
    )
    (comp (ref "R50")
      (value "47K")
      (footprint "2012[0805]_Res")
      (description "0805")
      (fields (field (name "Comment") "47k") (field (name "PUBLISHER") "Altium Limited"))
      (libsource (lib "") (part "Res1_2"))
    )
    (comp (ref "R51")
      (value "10k")
      (footprint "2012[0805]_Res")
      (description "0805")
      (fields
        (field (name "MANUFACTURER") "Panasonic Electronic Components")
        (field (name "MANUFACTURER PART NUMBER") "ERJ-6GEYJ103V")
        (field (name "PUBLISHER") "Altium Limited")
      )
      (libsource (lib "") (part "Res1_2"))
    )
    (comp (ref "R52")
      (value "10k")
      (footprint "2012[0805]_Res")
      (description "0805")
      (fields
        (field (name "MANUFACTURER") "Panasonic Electronic Components")
        (field (name "MANUFACTURER PART NUMBER") "ERJ-6GEYJ103V")
        (field (name "PUBLISHER") "Altium Limited")
      )
      (libsource (lib "") (part "Res1_2"))
    )
    (comp (ref "R53")
      (value "10k")
      (footprint "2012[0805]_Res")
      (description "0805")
      (fields
        (field (name "MANUFACTURER") "Panasonic Electronic Components")
        (field (name "MANUFACTURER PART NUMBER") "ERJ-6GEYJ103V")
        (field (name "PUBLISHER") "Altium Limited")
      )
      (libsource (lib "") (part "Res1_2"))
    )
    (comp (ref "R54")
      (value "10k")
      (footprint "2012[0805]_Res")
      (description "0805")
      (fields
        (field (name "MANUFACTURER") "Panasonic Electronic Components")
        (field (name "MANUFACTURER PART NUMBER") "ERJ-6GEYJ103V")
        (field (name "PUBLISHER") "Altium Limited")
      )
      (libsource (lib "") (part "Res1_2"))
    )
    (comp (ref "R55")
      (value "10k")
      (footprint "2012[0805]_Res")
      (description "0805")
      (fields
        (field (name "MANUFACTURER") "Panasonic Electronic Components")
        (field (name "MANUFACTURER PART NUMBER") "ERJ-6GEYJ103V")
        (field (name "PUBLISHER") "Altium Limited")
      )
      (libsource (lib "") (part "Res1_2"))
    )
    (comp (ref "R56")
      (value "10k")
      (footprint "2012[0805]_Res")
      (description "0805")
      (fields
        (field (name "MANUFACTURER") "Panasonic Electronic Components")
        (field (name "MANUFACTURER PART NUMBER") "ERJ-6GEYJ103V")
        (field (name "PUBLISHER") "Altium Limited")
      )
      (libsource (lib "") (part "Res1_2"))
    )
    (comp (ref "R57")
      (value "10k")
      (footprint "2012[0805]_Res")
      (description "0805")
      (fields
        (field (name "MANUFACTURER") "Panasonic Electronic Components")
        (field (name "MANUFACTURER PART NUMBER") "ERJ-6GEYJ103V")
        (field (name "PUBLISHER") "Altium Limited")
      )
      (libsource (lib "") (part "Res1_2"))
    )
    (comp (ref "R58")
      (value "47k")
      (footprint "2012[0805]_Res")
      (description "0805")
      (fields
        (field (name "MANUFACTURER") "Panasonic Electronic Components")
        (field (name "MANUFACTURER PART NUMBER") "ERJ-6GEYJ473V")
        (field (name "PUBLISHER") "Altium Limited")
      )
      (libsource (lib "") (part "Res1_2"))
    )
    (comp (ref "R59")
      (value "47k")
      (footprint "2012[0805]_Res")
      (description "0805")
      (fields
        (field (name "MANUFACTURER") "Panasonic Electronic Components")
        (field (name "MANUFACTURER PART NUMBER") "ERJ-6GEYJ473V")
        (field (name "PUBLISHER") "Altium Limited")
      )
      (libsource (lib "") (part "Res1_2"))
    )
    (comp (ref "R60")
      (value "1K")
      (footprint "2012[0805]_Res")
      (description "0805")
      (fields (field (name "Comment") "1k") (field (name "PUBLISHER") "Altium Limited"))
      (libsource (lib "") (part "Res1_2"))
    )
    (comp (ref "R61")
      (value "1K")
      (footprint "2012[0805]_Res")
      (description "0805")
      (fields (field (name "Comment") "1k") (field (name "PUBLISHER") "Altium Limited"))
      (libsource (lib "") (part "Res1_2"))
    )
    (comp (ref "R62")
      (value "47K")
      (footprint "2012[0805]_Res")
      (description "0805")
      (fields (field (name "Comment") "47k") (field (name "PUBLISHER") "Altium Limited"))
      (libsource (lib "") (part "Res1_2"))
    )
    (comp (ref "R63")
      (value "1K")
      (footprint "2012[0805]_Res")
      (description "0805")
      (fields (field (name "Comment") "1k") (field (name "PUBLISHER") "Altium Limited"))
      (libsource (lib "") (part "Res1_2"))
    )
    (comp (ref "R64")
      (value "1K")
      (footprint "2012[0805]_Res")
      (description "0805")
      (fields (field (name "Comment") "1k") (field (name "PUBLISHER") "Altium Limited"))
      (libsource (lib "") (part "Res1_2"))
    )
    (comp (ref "R65")
      (value "1K")
      (footprint "2012[0805]_Res")
      (description "0805")
      (fields (field (name "Comment") "1k") (field (name "PUBLISHER") "Altium Limited"))
      (libsource (lib "") (part "Res1_2"))
    )
    (comp (ref "R66")
      (value "1K")
      (footprint "2012[0805]_Res")
      (description "0805")
      (fields (field (name "Comment") "1k") (field (name "PUBLISHER") "Altium Limited"))
      (libsource (lib "") (part "Res1_2"))
    )
    (comp (ref "R68")
      (value "4K7")
      (footprint "2012[0805]_Res")
      (description "0805")
      (fields (field (name "Comment") "4k7") (field (name "PUBLISHER") "Altium Limited"))
      (libsource (lib "") (part "Res1_2"))
    )
    (comp (ref "R69")
      (value "1K")
      (footprint "2012[0805]_Res")
      (description "0805")
      (fields (field (name "Comment") "1k") (field (name "PUBLISHER") "Altium Limited"))
      (libsource (lib "") (part "Res1_2"))
    )
    (comp (ref "R70")
      (value "4k7")
      (footprint "2012[0805]_Res")
      (description "0805")
      (fields (field (name "PUBLISHER") "Altium Limited"))
      (libsource (lib "Miscellaneous Devices") (part "Res3"))
    )
    (comp (ref "R71")
      (value "4k7")
      (footprint "2012[0805]_Res")
      (description "0805")
      (fields (field (name "PUBLISHER") "Altium Limited"))
      (libsource (lib "Miscellaneous Devices") (part "Res3"))
    )
    (comp (ref "R72")
      (value "4k7")
      (footprint "2012[0805]_Res")
      (description "0805")
      (fields (field (name "PUBLISHER") "Altium Limited"))
      (libsource (lib "Miscellaneous Devices") (part "Res3"))
    )
    (comp (ref "R73")
      (value "4k7")
      (footprint "2012[0805]_Res")
      (description "0805")
      (fields (field (name "PUBLISHER") "Altium Limited"))
      (libsource (lib "Miscellaneous Devices") (part "Res3"))
    )
    (comp (ref "R74")
      (value "4k7")
      (footprint "2012[0805]_Res")
      (description "0805")
      (fields (field (name "PUBLISHER") "Altium Limited"))
      (libsource (lib "Miscellaneous Devices") (part "Res3"))
    )
    (comp (ref "R75")
      (value "4k7")
      (footprint "2012[0805]_Res")
      (description "0805")
      (fields (field (name "PUBLISHER") "Altium Limited"))
      (libsource (lib "Miscellaneous Devices") (part "Res3"))
    )
    (comp (ref "R76")
      (value "4k7")
      (footprint "2012[0805]_Res")
      (description "0805")
      (fields (field (name "PUBLISHER") "Altium Limited"))
      (libsource (lib "Miscellaneous Devices") (part "Res3"))
    )
    (comp (ref "R77")
      (value "4k7")
      (footprint "2012[0805]_Res")
      (description "0805")
      (fields (field (name "PUBLISHER") "Altium Limited"))
      (libsource (lib "Miscellaneous Devices") (part "Res3"))
    )
    (comp (ref "R78")
      (value "330R")
      (footprint "2012[0805]_Res")
      (description "0805")
      (fields (field (name "PUBLISHER") "Altium Limited"))
      (libsource (lib "") (part "Res1_2"))
    )
    (comp (ref "R79")
      (value "10k")
      (footprint "2012[0805]_Res")
      (description "0805")
      (fields
        (field (name "MANUFACTURER") "Panasonic Electronic Components")
        (field (name "MANUFACTURER PART NUMBER") "ERJ-6GEYJ103V")
        (field (name "PUBLISHER") "Altium Limited")
      )
      (libsource (lib "") (part "Res1_2"))
    )
    (comp (ref "R80")
      (value "10K")
      (footprint "2012[0805]_Res")
      (description "0805")
      (fields (field (name "Comment") "10k") (field (name "PUBLISHER") "Altium Limited"))
      (libsource (lib "") (part "Res1_2"))
    )
    (comp (ref "R81")
      (value "10K")
      (footprint "2012[0805]_Res")
      (description "0805")
      (fields (field (name "Comment") "10k") (field (name "PUBLISHER") "Altium Limited"))
      (libsource (lib "") (part "Res1_2"))
    )
    (comp (ref "R82")
      (value "10K")
      (footprint "2012[0805]_Res")
      (description "0805")
      (fields (field (name "Comment") "10k") (field (name "PUBLISHER") "Altium Limited"))
      (libsource (lib "") (part "Res1_2"))
    )
    (comp (ref "R83")
      (value "47k")
      (footprint "2012[0805]_Res")
      (description "0805")
      (fields
        (field (name "MANUFACTURER") "Panasonic Electronic Components")
        (field (name "MANUFACTURER PART NUMBER") "ERJ-6GEYJ473V")
        (field (name "PUBLISHER") "Altium Limited")
      )
      (libsource (lib "") (part "Res1_2"))
    )
    (comp (ref "R84")
      (value "47k")
      (footprint "2012[0805]_Res")
      (description "0805")
      (fields
        (field (name "MANUFACTURER") "Panasonic Electronic Components")
        (field (name "MANUFACTURER PART NUMBER") "ERJ-6GEYJ473V")
        (field (name "PUBLISHER") "Altium Limited")
      )
      (libsource (lib "") (part "Res1_2"))
    )
    (comp (ref "R85")
      (value "47k")
      (footprint "2012[0805]_Res")
      (description "0805")
      (fields
        (field (name "MANUFACTURER") "Panasonic Electronic Components")
        (field (name "MANUFACTURER PART NUMBER") "ERJ-6GEYJ473V")
        (field (name "PUBLISHER") "Altium Limited")
      )
      (libsource (lib "") (part "Res1_2"))
    )
    (comp (ref "R88")
      (value "47K")
      (footprint "2012[0805]_Res")
      (description "0805")
      (fields (field (name "Comment") "47k") (field (name "PUBLISHER") "Altium Limited"))
      (libsource (lib "Miscellaneous Devices") (part "Res3"))
    )
    (comp (ref "R89")
      (value "1K")
      (footprint "2012[0805]_Res")
      (description "1k")
      (fields (field (name "Comment") "0805") (field (name "PUBLISHER") "Altium Limited"))
      (libsource (lib "") (part "Res1_2"))
    )
    (comp (ref "R90")
      (value "270R")
      (footprint "2012[0805]_Res")
      (description "0805")
      (fields (field (name "PUBLISHER") "Altium Limited"))
      (libsource (lib "") (part "Res1_2"))
    )
    (comp (ref "R91")
      (value "270R")
      (footprint "2012[0805]_Res")
      (description "0805")
      (fields (field (name "PUBLISHER") "Altium Limited"))
      (libsource (lib "") (part "Res1_2"))
    )
    (comp (ref "R95a")
      (value "1K")
      (footprint "2012[0805]_Res")
      (description "0805")
      (fields (field (name "Comment") "10k") (field (name "PUBLISHER") "Altium Limited"))
      (libsource (lib "") (part "Res1_2"))
    )
    (comp (ref "R95b")
      (value "1K")
      (footprint "2012[0805]_Res")
      (description "0805")
      (fields (field (name "Comment") "10k") (field (name "PUBLISHER") "Altium Limited"))
      (libsource (lib "") (part "Res1_2"))
    )
    (comp (ref "R96")
      (value "22K")
      (footprint "2012[0805]_Res")
      (description "0805")
      (fields (field (name "Comment") "22k") (field (name "PUBLISHER") "Altium Limited"))
      (libsource (lib "") (part "Res1_2"))
    )
    (comp (ref "R97")
      (value "47K")
      (footprint "2012[0805]_Res")
      (description "0805")
      (fields (field (name "Comment") "47k") (field (name "PUBLISHER") "Altium Limited"))
      (libsource (lib "") (part "Res1_2"))
    )
    (comp (ref "R98")
      (value "10K")
      (footprint "2012[0805]_Res")
      (description "0805")
      (fields (field (name "Comment") "10k") (field (name "PUBLISHER") "Altium Limited"))
      (libsource (lib "") (part "Res1_2"))
    )
    (comp (ref "R99")
      (value "10R")
      (footprint "2012[0805]_Res")
      (description "0805")
      (fields (field (name "PUBLISHER") "Altium Limited"))
      (libsource (lib "") (part "Res1_2"))
    )
    (comp (ref "TH1")
      (value "Res Thermal")
      (footprint "HDR1X2")
      (description "Thermistor")
      (fields (field (name "PUBLISHER") "Altium Limited"))
      (libsource (lib "Miscellaneous Devices") (part "Res Thermal"))
    )
    (comp (ref "TH2")
      (value "Res Thermal")
      (footprint "HDR1X2")
      (description "Thermistor")
      (fields (field (name "PUBLISHER") "Altium Limited"))
      (libsource (lib "Miscellaneous Devices") (part "Res Thermal"))
    )
    (comp (ref "TH3")
      (value "Res Thermal")
      (footprint "HDR1X2")
      (description "Thermistor")
      (fields (field (name "PUBLISHER") "Altium Limited"))
      (libsource (lib "Miscellaneous Devices") (part "Res Thermal"))
    )
    (comp (ref "TH4")
      (value "Res Thermal")
      (footprint "HDR1X2")
      (description "Thermistor")
      (fields (field (name "PUBLISHER") "Altium Limited"))
      (libsource (lib "Miscellaneous Devices") (part "Res Thermal"))
    )
    (comp (ref "TH5")
      (value "Res Thermal")
      (footprint "HDR1X2")
      (description "Thermistor")
      (fields (field (name "PUBLISHER") "Altium Limited"))
      (libsource (lib "Miscellaneous Devices") (part "Res Thermal"))
    )
    (comp (ref "TH6")
      (value "Res Thermal")
      (footprint "HDR1X2")
      (description "Thermistor")
      (fields (field (name "PUBLISHER") "Altium Limited"))
      (libsource (lib "Miscellaneous Devices") (part "Res Thermal"))
    )
    (comp (ref "TH7")
      (value "Res Thermal")
      (footprint "HDR1X2")
      (description "Thermistor")
      (fields (field (name "PUBLISHER") "Altium Limited"))
      (libsource (lib "Miscellaneous Devices") (part "Res Thermal"))
    )
    (comp (ref "TH8")
      (value "Res Thermal")
      (footprint "HDR1X2")
      (description "Thermistor")
      (fields (field (name "PUBLISHER") "Altium Limited"))
      (libsource (lib "Miscellaneous Devices") (part "Res Thermal"))
    )
    (comp (ref "U1")
      (value "ATmega64M1-16AU")
      (footprint "32A_N")
      (description "8-Bit AVR Microcontroller with 8K Bytes of In-System Programmable Flash Memory")
      (fields (field (name "PUBLISHER") "Altium Limited"))
      (libsource (lib "Atmel Microcontroller 8-Bit AVR") (part "ATmega8-16AC"))
    )
    (comp (ref "U5")
      (value "ISO1050")
      (footprint "DUB8")
      (description "Isolated CAN transceiver")
      (fields
        (field (name "MANUFACTURER") "Texas Instruments")
        (field (name "MANUFACTURER PART NUMBER") "ISO1050DUBR")
        (field (name "PUBLISHER") "Altium Limited")
      )
      (libsource (lib "Atmel Microcontroller 8-Bit AVR") (part "AT90S2343-10SI"))
    )
    (comp (ref "U6")
      (value "MC33174D")
      (footprint "SO14_N")
      (description "Low-Power Quad Bipolar Operational Amplifier")
      (fields
        (field (name "MANUFACTURER") "STMicroelectronics")
        (field (name "MANUFACTURER PART NUMBER") "MC33174DT")
        (field (name "PUBLISHER") "Altium Limited")
      )
      (libsource (lib "ST Operational Amplifier") (part "MC33174D"))
    )
    (comp (ref "U7")
      (value "MC33174D")
      (footprint "SO14_N")
      (description "Low-Power Quad Bipolar Operational Amplifier")
      (fields
        (field (name "MANUFACTURER") "STMicroelectronics")
        (field (name "MANUFACTURER PART NUMBER") "MC33174DT")
        (field (name "PUBLISHER") "Altium Limited")
      )
      (libsource (lib "") (part "MC33174D_3"))
    )
    (comp (ref "U10")
      (value "Optoisolator1")
      (footprint "SO4")
      (description "4-Pin Phototransistor Optocoupler")
      (fields
        (field (name "MANUFACTURER") "Vishay Semiconductor Opto Division")
        (field (name "MANUFACTURER PART NUMBER") "TCMT1600")
        (field (name "PUBLISHER") "Altium Limited")
      )
      (libsource (lib "Miscellaneous Devices") (part "Optoisolator1"))
    )
    (comp (ref "U11")
      (value "Optoisolator1")
      (footprint "SO4")
      (description "4-Pin Phototransistor Optocoupler")
      (fields
        (field (name "MANUFACTURER") "Vishay Semiconductor Opto Division")
        (field (name "MANUFACTURER PART NUMBER") "TCMT1600")
        (field (name "PUBLISHER") "Altium Limited")
      )
      (libsource (lib "Miscellaneous Devices") (part "Optoisolator1"))
    )
    (comp (ref "U12")
      (value "Optoisolator3")
      (footprint "SO4")
      (description "4-Pin Phototransistor Optocoupler")
      (fields
        (field (name "MANUFACTURER") "Vishay Semiconductor Opto Division")
        (field (name "MANUFACTURER PART NUMBER") "TCMT1600")
        (field (name "PUBLISHER") "Altium Limited")
      )
      (libsource (lib "") (part "Optoisolator1_1"))
    )
    (comp (ref "U13")
      (value "Optoisolator4")
      (footprint "SO4")
      (description "4-Pin Phototransistor Optocoupler")
      (fields
        (field (name "MANUFACTURER") "Vishay Semiconductor Opto Division")
        (field (name "MANUFACTURER PART NUMBER") "TCMT1600")
        (field (name "PUBLISHER") "Altium Limited")
      )
      (libsource (lib "Miscellaneous Devices") (part "Optoisolator1"))
    )
    (comp (ref "U14")
      (value "Optoisolator1")
      (footprint "SO4")
      (description "4-Pin Phototransistor Optocoupler")
      (fields
        (field (name "MANUFACTURER") "Vishay Semiconductor Opto Division")
        (field (name "MANUFACTURER PART NUMBER") "TCMT1600")
        (field (name "PUBLISHER") "Altium Limited")
      )
      (libsource (lib "") (part "Optoisolator1_1"))
    )
    (comp (ref "U15")
      (value "Optoisolator1")
      (footprint "SO4")
      (description "4-Pin Phototransistor Optocoupler")
      (fields
        (field (name "MANUFACTURER") "Vishay Semiconductor Opto Division")
        (field (name "MANUFACTURER PART NUMBER") "TCMT1600")
        (field (name "PUBLISHER") "Altium Limited")
      )
      (libsource (lib "Miscellaneous Devices") (part "Optoisolator1"))
    )
    (comp (ref "U16")
      (value "Optoisolator1")
      (footprint "SO4")
      (description "4-Pin Phototransistor Optocoupler")
      (fields
        (field (name "MANUFACTURER") "Vishay Semiconductor Opto Division")
        (field (name "MANUFACTURER PART NUMBER") "TCMT1600")
        (field (name "PUBLISHER") "Altium Limited")
      )
      (libsource (lib "Miscellaneous Devices") (part "Optoisolator1"))
    )
    (comp (ref "U17")
      (value "Optoisolator1")
      (footprint "SO4")
      (description "4-Pin Phototransistor Optocoupler")
      (fields
        (field (name "MANUFACTURER") "Vishay Semiconductor Opto Division")
        (field (name "MANUFACTURER PART NUMBER") "TCMT1600")
        (field (name "PUBLISHER") "Altium Limited")
      )
      (libsource (lib "Miscellaneous Devices") (part "Optoisolator1"))
    )
    (comp (ref "U18")
      (value "Optoisolator1")
      (footprint "SO4")
      (description "4-Pin Phototransistor Optocoupler")
      (fields
        (field (name "MANUFACTURER") "Vishay Semiconductor Opto Division")
        (field (name "MANUFACTURER PART NUMBER") "TCMT1600")
        (field (name "PUBLISHER") "Altium Limited")
      )
      (libsource (lib "Miscellaneous Devices") (part "Optoisolator1"))
    )
    (comp (ref "U19")
      (value "Optoisolator1")
      (footprint "SO4")
      (description "4-Pin Phototransistor Optocoupler")
      (fields
        (field (name "MANUFACTURER") "Vishay Semiconductor Opto Division")
        (field (name "MANUFACTURER PART NUMBER") "TCMT1600")
        (field (name "PUBLISHER") "Altium Limited")
      )
      (libsource (lib "Miscellaneous Devices") (part "Optoisolator1"))
    )
    (comp (ref "U20")
      (value "74HC4051")
      (footprint "SO-16")
      (description "Wideband Dual-Channel Linear Multiplier/Divider")
      (fields
        (field (name "MANUFACTURER") "NXP Semiconductors")
        (field (name "MANUFACTURER PART NUMBER") "74HC4051D,653")
        (field (name "PUBLISHER") "Altium Limited")
      )
      (libsource (lib "AD Analog Multiplier Divider") (part "AD539KN"))
    )
    (comp (ref "U21")
      (value "Optoisolator1")
      (footprint "SO4")
      (description "4-Pin Phototransistor Optocoupler")
      (fields
        (field (name "MANUFACTURER") "Vishay Semiconductor Opto Division")
        (field (name "MANUFACTURER PART NUMBER") "TCMT1600")
        (field (name "PUBLISHER") "Altium Limited")
      )
      (libsource (lib "Miscellaneous Devices") (part "Optoisolator1"))
    )
    (comp (ref "VR1")
      (value "5V LDO INH Reg")
      (footprint "DPAK-5")
      (description "IC REG LDO 5V 0.4A TO252-5")
      (fields
        (field (name "MANUFACTURER") "Infineon Technologies")
        (field (name "MANUFACTURER PART NUMBER") "IFX25401TE V50")
      )
      (libsource (lib "Schlib1") (part "IFX25401TE V50"))
    )
    (comp (ref "VR2")
      (value "MC78M05BDTRK")
      (footprint "FootprintLibrary:D2PAK")
      (description "Three-Terminal Medium Current Positive Voltage Regulator")
      (fields
        (field (name "MANUFACTURER") "ON Semiconductor")
        (field (name "MANUFACTURER PART NUMBER") "MC78M05CDTRKG")
        (field (name "PUBLISHER") "Altium Limited")
      )
      (libsource (lib "ON Semi Power Mgt Voltage Regulator") (part "MC78M05BDTRK"))
    )
    (comp (ref "Y1")
      (value "16MHz")
      (footprint "Crystal")
      (description "Crystal Oscillator")
      (fields
        (field (name "MANUFACTURER") "Abracon LLC")
        (field (name "MANUFACTURER PART NUMBER") "ABLS-16.000MHZ-D-4-T")
        (field (name "PUBLISHER") "Altium Limited")
      )
      (libsource (lib "Miscellaneous Devices") (part "XTAL"))
    )
  )
  (nets
    (net (code "1") (name "/5V_GLV") (class "Default")
      (node (ref "C14") (pin "2") (pinfunction "2_2") (pintype "passive"))
      (node (ref "C17") (pin "2") (pinfunction "2_2") (pintype "passive"))
      (node (ref "U12") (pin "1") (pinfunction "A_1") (pintype "passive"))
      (node (ref "U13") (pin "4") (pinfunction "C_4") (pintype "passive"))
      (node (ref "U5") (pin "8") (pinfunction "VCC2_8") (pintype "power_in"))
      (node (ref "VR2") (pin "3") (pinfunction "OUT_3") (pintype "power_in"))
    )
    (net (code "2") (name "/AGND") (class "Default")
      (node (ref "R99") (pin "2") (pinfunction "2_2") (pintype "passive"))
      (node (ref "U1") (pin "20") (pinfunction "AGND_20") (pintype "power_in"))
    )
    (net (code "3") (name "/AREF") (class "Default")
      (node (ref "C39") (pin "1") (pinfunction "1_1") (pintype "passive"))
      (node (ref "U1") (pin "21") (pinfunction "AREF_21") (pintype "power_in"))
    )
    (net (code "4") (name "/AVCC") (class "Default")
      (node (ref "C40") (pin "1") (pinfunction "1_1") (pintype "passive"))
      (node (ref "L1") (pin "2") (pinfunction "2_2") (pintype "passive"))
      (node (ref "U1") (pin "19") (pinfunction "AVCC_19") (pintype "power_in"))
    )
    (net (code "5") (name "/BAL_1") (class "Default")
      (node (ref "Q8") (pin "2") (pinfunction "D_2") (pintype "passive"))
      (node (ref "R1") (pin "3") (pinfunction "2_3") (pintype "passive"))
    )
    (net (code "6") (name "/BAL_2") (class "Default")
      (node (ref "Q7") (pin "2") (pinfunction "D_2") (pintype "passive"))
      (node (ref "R2") (pin "3") (pinfunction "2_3") (pintype "passive"))
    )
    (net (code "7") (name "/BAL_3") (class "Default")
      (node (ref "Q6") (pin "2") (pinfunction "D_2") (pintype "passive"))
      (node (ref "R3") (pin "3") (pinfunction "2_3") (pintype "passive"))
    )
    (net (code "8") (name "/BAL_4") (class "Default")
      (node (ref "Q5") (pin "2") (pinfunction "D_2") (pintype "passive"))
      (node (ref "R4") (pin "3") (pinfunction "2_3") (pintype "passive"))
    )
    (net (code "9") (name "/BAL_5") (class "Default")
      (node (ref "Q4") (pin "2") (pinfunction "D_2") (pintype "passive"))
      (node (ref "R5") (pin "3") (pinfunction "2_3") (pintype "passive"))
    )
    (net (code "10") (name "/BAL_6") (class "Default")
      (node (ref "Q3") (pin "2") (pinfunction "D_2") (pintype "passive"))
      (node (ref "R6") (pin "3") (pinfunction "2_3") (pintype "passive"))
    )
    (net (code "11") (name "/BAL_7") (class "Default")
      (node (ref "Q2") (pin "2") (pinfunction "D_2") (pintype "passive"))
      (node (ref "R7") (pin "3") (pinfunction "2_3") (pintype "passive"))
    )
    (net (code "12") (name "/BAL_8") (class "Default")
      (node (ref "Q1") (pin "2") (pinfunction "D_2") (pintype "passive"))
      (node (ref "R8") (pin "3") (pinfunction "2_3") (pintype "passive"))
    )
    (net (code "13") (name "/CANH") (class "Default")
      (node (ref "J2") (pin "5") (pinfunction "5_5") (pintype "passive"))
      (node (ref "J3") (pin "5") (pinfunction "5_5") (pintype "passive"))
      (node (ref "U5") (pin "7") (pinfunction "CAN_HI_7") (pintype "bidirectional"))
    )
    (net (code "14") (name "/CANL") (class "Default")
      (node (ref "J2") (pin "4") (pinfunction "4_4") (pintype "passive"))
      (node (ref "J3") (pin "4") (pinfunction "4_4") (pintype "passive"))
      (node (ref "U5") (pin "6") (pinfunction "CAN_LO_6") (pintype "bidirectional"))
    )
    (net (code "15") (name "/CMU_ACTIVE_GLV") (class "Default")
      (node (ref "R61") (pin "1") (pinfunction "1_1") (pintype "passive"))
      (node (ref "U12") (pin "2") (pinfunction "K_2") (pintype "passive"))
    )
    (net (code "16") (name "/CMU_ACTIVE_HV") (class "Default")
      (node (ref "R62") (pin "1") (pinfunction "1_1") (pintype "passive"))
      (node (ref "U12") (pin "3") (pinfunction "E_3") (pintype "passive"))
      (node (ref "VR1") (pin "2") (pinfunction "EN_2") (pintype "passive"))
    )
    (net (code "17") (name "/CMU_PWR2") (class "Default")
      (node (ref "R60") (pin "1") (pinfunction "1_1") (pintype "passive"))
      (node (ref "U12") (pin "4") (pinfunction "C_4") (pintype "passive"))
    )
    (net (code "18") (name "/EMIT_1") (class "Default")
      (node (ref "R79") (pin "2") (pinfunction "2_2") (pintype "passive"))
      (node (ref "U21") (pin "3") (pinfunction "E_3") (pintype "passive"))
    )
    (net (code "19") (name "/EMIT_2") (class "Default")
      (node (ref "R51") (pin "2") (pinfunction "2_2") (pintype "passive"))
      (node (ref "U19") (pin "3") (pinfunction "E_3") (pintype "passive"))
    )
    (net (code "20") (name "/EMIT_3") (class "Default")
      (node (ref "R52") (pin "2") (pinfunction "2_2") (pintype "passive"))
      (node (ref "U18") (pin "3") (pinfunction "E_3") (pintype "passive"))
    )
    (net (code "21") (name "/EMIT_4") (class "Default")
      (node (ref "R53") (pin "2") (pinfunction "2_2") (pintype "passive"))
      (node (ref "U17") (pin "3") (pinfunction "E_3") (pintype "passive"))
    )
    (net (code "22") (name "/EMIT_5") (class "Default")
      (node (ref "R54") (pin "2") (pinfunction "2_2") (pintype "passive"))
      (node (ref "U16") (pin "3") (pinfunction "E_3") (pintype "passive"))
    )
    (net (code "23") (name "/EMIT_6") (class "Default")
      (node (ref "R55") (pin "2") (pinfunction "2_2") (pintype "passive"))
      (node (ref "U15") (pin "3") (pinfunction "E_3") (pintype "passive"))
    )
    (net (code "24") (name "/EMIT_7") (class "Default")
      (node (ref "R56") (pin "2") (pinfunction "2_2") (pintype "passive"))
      (node (ref "U11") (pin "3") (pinfunction "E_3") (pintype "passive"))
    )
    (net (code "25") (name "/EMIT_8") (class "Default")
      (node (ref "R57") (pin "2") (pinfunction "2_2") (pintype "passive"))
      (node (ref "U10") (pin "3") (pinfunction "E_3") (pintype "passive"))
    )
    (net (code "26") (name "/GATE_1") (class "Default")
      (node (ref "Q8") (pin "1") (pinfunction "G_1") (pintype "passive"))
      (node (ref "R41") (pin "2") (pinfunction "2_2") (pintype "passive"))
      (node (ref "R79") (pin "1") (pinfunction "1_1") (pintype "passive"))
    )
    (net (code "27") (name "/GATE_2") (class "Default")
      (node (ref "Q7") (pin "1") (pinfunction "G_1") (pintype "passive"))
      (node (ref "R49") (pin "2") (pinfunction "2_2") (pintype "passive"))
      (node (ref "R51") (pin "1") (pinfunction "1_1") (pintype "passive"))
    )
    (net (code "28") (name "/GATE_3") (class "Default")
      (node (ref "Q6") (pin "1") (pinfunction "G_1") (pintype "passive"))
      (node (ref "R32") (pin "2") (pinfunction "2_2") (pintype "passive"))
      (node (ref "R52") (pin "1") (pinfunction "1_1") (pintype "passive"))
    )
    (net (code "29") (name "/GATE_4") (class "Default")
      (node (ref "Q5") (pin "1") (pinfunction "G_1") (pintype "passive"))
      (node (ref "R53") (pin "1") (pinfunction "1_1") (pintype "passive"))
      (node (ref "R58") (pin "1") (pinfunction "1_1") (pintype "passive"))
    )
    (net (code "30") (name "/GATE_5") (class "Default")
      (node (ref "Q4") (pin "1") (pinfunction "G_1") (pintype "passive"))
      (node (ref "R54") (pin "1") (pinfunction "1_1") (pintype "passive"))
      (node (ref "R59") (pin "2") (pinfunction "2_2") (pintype "passive"))
    )
    (net (code "31") (name "/GATE_6") (class "Default")
      (node (ref "Q3") (pin "1") (pinfunction "G_1") (pintype "passive"))
      (node (ref "R55") (pin "1") (pinfunction "1_1") (pintype "passive"))
      (node (ref "R83") (pin "2") (pinfunction "2_2") (pintype "passive"))
    )
    (net (code "32") (name "/GATE_7") (class "Default")
      (node (ref "Q2") (pin "1") (pinfunction "G_1") (pintype "passive"))
      (node (ref "R56") (pin "1") (pinfunction "1_1") (pintype "passive"))
      (node (ref "R84") (pin "2") (pinfunction "2_2") (pintype "passive"))
    )
    (net (code "33") (name "/GATE_8") (class "Default")
      (node (ref "Q1") (pin "1") (pinfunction "G_1") (pintype "passive"))
      (node (ref "R57") (pin "1") (pinfunction "1_1") (pintype "passive"))
      (node (ref "R85") (pin "2") (pinfunction "2_2") (pintype "passive"))
    )
    (net (code "34") (name "/GLV") (class "Default")
      (node (ref "C15") (pin "1") (pinfunction "1_1") (pintype "passive"))
      (node (ref "J2") (pin "2") (pinfunction "2_2") (pintype "passive"))
      (node (ref "J3") (pin "2") (pinfunction "2_2") (pintype "passive"))
      (node (ref "VR2") (pin "1") (pinfunction "IN_1") (pintype "power_in"))
    )
    (net (code "35") (name "/LED_1") (class "Default")
      (node (ref "D1") (pin "2") (pinfunction "K_2") (pintype "passive"))
      (node (ref "R90") (pin "2") (pinfunction "2_2") (pintype "passive"))
    )
    (net (code "36") (name "/LED_PWR") (class "Default")
      (node (ref "D2") (pin "2") (pinfunction "K_2") (pintype "passive"))
      (node (ref "R91") (pin "1") (pinfunction "1_1") (pintype "passive"))
    )
    (net (code "37") (name "/MISO") (class "Default")
      (node (ref "J1") (pin "1") (pinfunction "1_1") (pintype "passive"))
      (node (ref "R81") (pin "1") (pinfunction "1_1") (pintype "passive"))
      (node (ref "U1") (pin "1") (pinfunction "PD2_(PSCIN2/MISO_A)_1") (pintype "input"))
    )
    (net (code "38") (name "/MOSI") (class "Default")
      (node (ref "J1") (pin "4") (pinfunction "4_4") (pintype "passive"))
      (node (ref "R82") (pin "1") (pinfunction "1_1") (pintype "passive"))
      (node (ref "U1") (pin "2") (pinfunction "PD3_(TXLIN/MOSI_A)_2") (pintype "output"))
    )
    (net (code "39") (name "/MUX_A") (class "Default")
      (node (ref "R80") (pin "2") (pinfunction "2_2") (pintype "passive"))
      (node (ref "U20") (pin "11") (pinfunction "A_11") (pintype "input"))
    )
    (net (code "40") (name "/MUX_B") (class "Default")
      (node (ref "R81") (pin "2") (pinfunction "2_2") (pintype "passive"))
      (node (ref "U20") (pin "10") (pinfunction "B_10") (pintype "input"))
    )
    (net (code "41") (name "/MUX_C") (class "Default")
      (node (ref "R82") (pin "2") (pinfunction "2_2") (pintype "passive"))
      (node (ref "U20") (pin "9") (pinfunction "C_9") (pintype "input"))
    )
    (net (code "42") (name "/MUX_COM") (class "Default")
      (node (ref "C20") (pin "2") (pinfunction "2_2") (pintype "passive"))
      (node (ref "R68") (pin "1") (pinfunction "1_1") (pintype "passive"))
      (node (ref "U1") (pin "13") (pinfunction "PD5_(ADC2)_13") (pintype "input"))
      (node (ref "U20") (pin "3") (pinfunction "COM_3") (pintype "output"))
    )
    (net (code "43") (name "/MUX_INH") (class "Default")
      (node (ref "R89") (pin "1") (pinfunction "1_1") (pintype "passive"))
      (node (ref "U20") (pin "6") (pinfunction "INH_6") (pintype "input"))
    )
    (net (code "44") (name "/N_Drain") (class "Default")
      (node (ref "Q9") (pin "3") (pinfunction "D_3") (pintype "passive"))
      (node (ref "R97") (pin "1") (pinfunction "1_1") (pintype "passive"))
    )
    (net (code "45") (name "/N_Gate") (class "Default")
      (node (ref "Q9") (pin "1") (pinfunction "G_1") (pintype "passive"))
      (node (ref "R50") (pin "2") (pinfunction "2_2") (pintype "passive"))
      (node (ref "R95a") (pin "2") (pinfunction "2_2") (pintype "passive"))
      (node (ref "R95b") (pin "2") (pinfunction "2_2") (pintype "passive"))
    )
    (net (code "46") (name "/OPAMP-N1") (class "Default")
      (node (ref "R40") (pin "1") (pinfunction "1_1") (pintype "passive"))
      (node (ref "U6") (pin "6") (pinfunction "IN-_6") (pintype "input"))
    )
    (net (code "47") (name "/OPAMP-N2") (class "Default")
      (node (ref "R39") (pin "1") (pinfunction "1_1") (pintype "passive"))
      (node (ref "R48") (pin "2") (pinfunction "2_2") (pintype "passive"))
      (node (ref "U6") (pin "9") (pinfunction "IN-_9") (pintype "input"))
    )
    (net (code "48") (name "/OPAMP-N3") (class "Default")
      (node (ref "R38") (pin "1") (pinfunction "1_1") (pintype "passive"))
      (node (ref "R47") (pin "2") (pinfunction "2_2") (pintype "passive"))
      (node (ref "U7") (pin "6") (pinfunction "IN-_6") (pintype "input"))
    )
    (net (code "49") (name "/OPAMP-N4") (class "Default")
      (node (ref "R37") (pin "1") (pinfunction "1_1") (pintype "passive"))
      (node (ref "R46") (pin "2") (pinfunction "2_2") (pintype "passive"))
      (node (ref "U7") (pin "9") (pinfunction "IN-_9") (pintype "input"))
    )
    (net (code "50") (name "/OPAMP-N5") (class "Default")
      (node (ref "R36") (pin "1") (pinfunction "1_1") (pintype "passive"))
      (node (ref "R45") (pin "2") (pinfunction "2_2") (pintype "passive"))
      (node (ref "U7") (pin "13") (pinfunction "IN-_13") (pintype "input"))
    )
    (net (code "51") (name "/OPAMP-N6") (class "Default")
      (node (ref "R35") (pin "1") (pinfunction "1_1") (pintype "passive"))
      (node (ref "R44") (pin "2") (pinfunction "2_2") (pintype "passive"))
      (node (ref "U7") (pin "2") (pinfunction "IN-_2") (pintype "input"))
    )
    (net (code "52") (name "/OPAMP-N7") (class "Default")
      (node (ref "R34") (pin "1") (pinfunction "1_1") (pintype "passive"))
      (node (ref "R43") (pin "2") (pinfunction "2_2") (pintype "passive"))
      (node (ref "U6") (pin "13") (pinfunction "IN-_13") (pintype "input"))
    )
    (net (code "53") (name "/OPAMP-N8") (class "Default")
      (node (ref "R33") (pin "1") (pinfunction "1_1") (pintype "passive"))
      (node (ref "R42") (pin "2") (pinfunction "2_2") (pintype "passive"))
      (node (ref "U6") (pin "2") (pinfunction "IN-_2") (pintype "input"))
    )
    (net (code "54") (name "/OPAMP-OUT1") (class "Default")
      (node (ref "R40") (pin "2") (pinfunction "2_2") (pintype "passive"))
      (node (ref "R77") (pin "1") (pinfunction "1_1") (pintype "passive"))
      (node (ref "U6") (pin "7") (pinfunction "OUT_7") (pintype "output"))
    )
    (net (code "55") (name "/OPAMP-OUT2") (class "Default")
      (node (ref "R39") (pin "2") (pinfunction "2_2") (pintype "passive"))
      (node (ref "R76") (pin "1") (pinfunction "1_1") (pintype "passive"))
      (node (ref "U6") (pin "8") (pinfunction "OUT_8") (pintype "output"))
    )
    (net (code "56") (name "/OPAMP-OUT3") (class "Default")
      (node (ref "R38") (pin "2") (pinfunction "2_2") (pintype "passive"))
      (node (ref "R75") (pin "1") (pinfunction "1_1") (pintype "passive"))
      (node (ref "U7") (pin "7") (pinfunction "OUT_7") (pintype "output"))
    )
    (net (code "57") (name "/OPAMP-OUT4") (class "Default")
      (node (ref "R37") (pin "2") (pinfunction "2_2") (pintype "passive"))
      (node (ref "R74") (pin "1") (pinfunction "1_1") (pintype "passive"))
      (node (ref "U7") (pin "8") (pinfunction "OUT_8") (pintype "output"))
    )
    (net (code "58") (name "/OPAMP-OUT5") (class "Default")
      (node (ref "R36") (pin "2") (pinfunction "2_2") (pintype "passive"))
      (node (ref "R73") (pin "1") (pinfunction "1_1") (pintype "passive"))
      (node (ref "U7") (pin "14") (pinfunction "OUT_14") (pintype "output"))
    )
    (net (code "59") (name "/OPAMP-OUT6") (class "Default")
      (node (ref "R35") (pin "2") (pinfunction "2_2") (pintype "passive"))
      (node (ref "R72") (pin "1") (pinfunction "1_1") (pintype "passive"))
      (node (ref "U7") (pin "1") (pinfunction "OUT_1") (pintype "output"))
    )
    (net (code "60") (name "/OPAMP-OUT7") (class "Default")
      (node (ref "R34") (pin "2") (pinfunction "2_2") (pintype "passive"))
      (node (ref "R71") (pin "1") (pinfunction "1_1") (pintype "passive"))
      (node (ref "U6") (pin "14") (pinfunction "OUT_14") (pintype "output"))
    )
    (net (code "61") (name "/OPAMP-OUT8") (class "Default")
      (node (ref "R33") (pin "2") (pinfunction "2_2") (pintype "passive"))
      (node (ref "R70") (pin "1") (pinfunction "1_1") (pintype "passive"))
      (node (ref "U6") (pin "1") (pinfunction "OUT_1") (pintype "output"))
    )
    (net (code "62") (name "/OPAMP-P1") (class "Default")
      (node (ref "R24") (pin "2") (pinfunction "2_2") (pintype "passive"))
      (node (ref "U6") (pin "5") (pinfunction "IN+_5") (pintype "input"))
    )
    (net (code "63") (name "/OPAMP-P2") (class "Default")
      (node (ref "R23") (pin "2") (pinfunction "2_2") (pintype "passive"))
      (node (ref "R31") (pin "1") (pinfunction "1_1") (pintype "passive"))
      (node (ref "U6") (pin "10") (pinfunction "IN+_10") (pintype "input"))
    )
    (net (code "64") (name "/OPAMP-P3") (class "Default")
      (node (ref "R22") (pin "2") (pinfunction "2_2") (pintype "passive"))
      (node (ref "R30") (pin "1") (pinfunction "1_1") (pintype "passive"))
      (node (ref "U7") (pin "5") (pinfunction "IN+_5") (pintype "input"))
    )
    (net (code "65") (name "/OPAMP-P4") (class "Default")
      (node (ref "R21") (pin "2") (pinfunction "2_2") (pintype "passive"))
      (node (ref "R29") (pin "1") (pinfunction "1_1") (pintype "passive"))
      (node (ref "U7") (pin "10") (pinfunction "IN+_10") (pintype "input"))
    )
    (net (code "66") (name "/OPAMP-P5") (class "Default")
      (node (ref "R20") (pin "2") (pinfunction "2_2") (pintype "passive"))
      (node (ref "R28") (pin "1") (pinfunction "1_1") (pintype "passive"))
      (node (ref "U7") (pin "12") (pinfunction "IN+_12") (pintype "input"))
    )
    (net (code "67") (name "/OPAMP-P6") (class "Default")
      (node (ref "R19") (pin "2") (pinfunction "2_2") (pintype "passive"))
      (node (ref "R27") (pin "1") (pinfunction "1_1") (pintype "passive"))
      (node (ref "U7") (pin "3") (pinfunction "IN+_3") (pintype "input"))
    )
    (net (code "68") (name "/OPAMP-P7") (class "Default")
      (node (ref "R18") (pin "2") (pinfunction "2_2") (pintype "passive"))
      (node (ref "R26") (pin "1") (pinfunction "1_1") (pintype "passive"))
      (node (ref "U6") (pin "12") (pinfunction "IN+_12") (pintype "input"))
    )
    (net (code "69") (name "/OPAMP-P8") (class "Default")
      (node (ref "R17") (pin "2") (pinfunction "2_2") (pintype "passive"))
      (node (ref "R25") (pin "1") (pinfunction "1_1") (pintype "passive"))
      (node (ref "U6") (pin "3") (pinfunction "IN+_3") (pintype "input"))
    )
    (net (code "70") (name "/OPTO-IN1") (class "Default")
      (node (ref "U1") (pin "32") (pinfunction "PD1_(PSCIN0)_32") (pintype "input"))
      (node (ref "U21") (pin "1") (pinfunction "A_1") (pintype "passive"))
    )
    (net (code "71") (name "/OPTO-IN2") (class "Default")
      (node (ref "U1") (pin "3") (pinfunction "PC1_(PSCIN1)_3") (pintype "input"))
      (node (ref "U19") (pin "1") (pinfunction "A_1") (pintype "passive"))
    )
    (net (code "72") (name "/OPTO-IN3") (class "Default")
      (node (ref "U1") (pin "8") (pinfunction "PB0_(PSCOUT2A)_8") (pintype "output"))
      (node (ref "U18") (pin "1") (pinfunction "A_1") (pintype "passive"))
    )
    (net (code "73") (name "/OPTO-IN4") (class "Default")
      (node (ref "U1") (pin "9") (pinfunction "PB1_(PSCOUT2B)_9") (pintype "output"))
      (node (ref "U17") (pin "1") (pinfunction "A_1") (pintype "passive"))
    )
    (net (code "74") (name "/OPTO-IN5") (class "Default")
      (node (ref "U1") (pin "15") (pinfunction "PD7_15") (pintype "bidirectional"))
      (node (ref "U16") (pin "1") (pinfunction "A_1") (pintype "passive"))
    )
    (net (code "75") (name "/OPTO-IN6") (class "Default")
      (node (ref "U1") (pin "23") (pinfunction "PB3_23") (pintype "output"))
      (node (ref "U15") (pin "1") (pinfunction "A_1") (pintype "passive"))
    )
    (net (code "76") (name "/OPTO-IN7") (class "Default")
      (node (ref "U1") (pin "24") (pinfunction "PB4_24") (pintype "output"))
      (node (ref "U11") (pin "1") (pinfunction "A_1") (pintype "passive"))
    )
    (net (code "77") (name "/OPTO-IN8") (class "Default")
      (node (ref "U1") (pin "25") (pinfunction "PC7_(D2A)_25") (pintype "bidirectional"))
      (node (ref "U10") (pin "1") (pinfunction "A_1") (pintype "passive"))
    )
    (net (code "78") (name "/OPTO-OUT1") (class "Default")
      (node (ref "R9") (pin "2") (pinfunction "2_2") (pintype "passive"))
      (node (ref "U21") (pin "2") (pinfunction "K_2") (pintype "passive"))
    )
    (net (code "79") (name "/OPTO-OUT2") (class "Default")
      (node (ref "R10") (pin "2") (pinfunction "2_2") (pintype "passive"))
      (node (ref "U19") (pin "2") (pinfunction "K_2") (pintype "passive"))
    )
    (net (code "80") (name "/OPTO-OUT3") (class "Default")
      (node (ref "R11") (pin "2") (pinfunction "2_2") (pintype "passive"))
      (node (ref "U18") (pin "2") (pinfunction "K_2") (pintype "passive"))
    )
    (net (code "81") (name "/OPTO-OUT4") (class "Default")
      (node (ref "R12") (pin "2") (pinfunction "2_2") (pintype "passive"))
      (node (ref "U17") (pin "2") (pinfunction "K_2") (pintype "passive"))
    )
    (net (code "82") (name "/OPTO-OUT5") (class "Default")
      (node (ref "R13") (pin "2") (pinfunction "2_2") (pintype "passive"))
      (node (ref "U16") (pin "2") (pinfunction "K_2") (pintype "passive"))
    )
    (net (code "83") (name "/OPTO-OUT6") (class "Default")
      (node (ref "R14") (pin "2") (pinfunction "2_2") (pintype "passive"))
      (node (ref "U15") (pin "2") (pinfunction "K_2") (pintype "passive"))
    )
    (net (code "84") (name "/OPTO-OUT7") (class "Default")
      (node (ref "R15") (pin "2") (pinfunction "2_2") (pintype "passive"))
      (node (ref "U11") (pin "2") (pinfunction "K_2") (pintype "passive"))
    )
    (net (code "85") (name "/OPTO-OUT8") (class "Default")
      (node (ref "R16") (pin "2") (pinfunction "2_2") (pintype "passive"))
      (node (ref "U10") (pin "2") (pinfunction "K_2") (pintype "passive"))
    )
    (net (code "86") (name "/PSEG_1") (class "Default")
      (node (ref "F1") (pin "2") (pinfunction "2_2") (pintype "passive"))
      (node (ref "F9") (pin "1") (pinfunction "1_1") (pintype "passive"))
      (node (ref "Q7") (pin "3") (pinfunction "S_3") (pintype "passive"))
      (node (ref "R1") (pin "1") (pinfunction "1_1") (pintype "passive"))
      (node (ref "R49") (pin "1") (pinfunction "1_1") (pintype "passive"))
      (node (ref "U21") (pin "4") (pinfunction "C_4") (pintype "passive"))
    )
    (net (code "87") (name "/PSEG_2") (class "Default")
      (node (ref "F10") (pin "1") (pinfunction "1_1") (pintype "passive"))
      (node (ref "F2") (pin "2") (pinfunction "2_2") (pintype "passive"))
      (node (ref "Q6") (pin "3") (pinfunction "S_3") (pintype "passive"))
      (node (ref "R2") (pin "1") (pinfunction "1_1") (pintype "passive"))
      (node (ref "R32") (pin "1") (pinfunction "1_1") (pintype "passive"))
      (node (ref "U19") (pin "4") (pinfunction "C_4") (pintype "passive"))
    )
    (net (code "88") (name "/PSEG_3") (class "Default")
      (node (ref "C99") (pin "2") (pinfunction "2_2") (pintype "passive"))
      (node (ref "F11") (pin "1") (pinfunction "1_1") (pintype "passive"))
      (node (ref "F3") (pin "2") (pinfunction "2_2") (pintype "passive"))
      (node (ref "Q5") (pin "3") (pinfunction "S_3") (pintype "passive"))
      (node (ref "R3") (pin "1") (pinfunction "1_1") (pintype "passive"))
      (node (ref "R58") (pin "2") (pinfunction "2_2") (pintype "passive"))
      (node (ref "R60") (pin "2") (pinfunction "2_2") (pintype "passive"))
      (node (ref "U18") (pin "4") (pinfunction "C_4") (pintype "passive"))
      (node (ref "VR1") (pin "1") (pinfunction "IN_1") (pintype "passive"))
    )
    (net (code "89") (name "/PSEG_4") (class "Default")
      (node (ref "F12") (pin "1") (pinfunction "1_1") (pintype "passive"))
      (node (ref "F4") (pin "2") (pinfunction "2_2") (pintype "passive"))
      (node (ref "Q4") (pin "3") (pinfunction "S_3") (pintype "passive"))
      (node (ref "R4") (pin "1") (pinfunction "1_1") (pintype "passive"))
      (node (ref "R59") (pin "1") (pinfunction "1_1") (pintype "passive"))
      (node (ref "U17") (pin "4") (pinfunction "C_4") (pintype "passive"))
    )
    (net (code "90") (name "/PSEG_5") (class "Default")
      (node (ref "F13") (pin "1") (pinfunction "1_1") (pintype "passive"))
      (node (ref "F5") (pin "2") (pinfunction "2_2") (pintype "passive"))
      (node (ref "Q3") (pin "3") (pinfunction "S_3") (pintype "passive"))
      (node (ref "R5") (pin "1") (pinfunction "1_1") (pintype "passive"))
      (node (ref "R83") (pin "1") (pinfunction "1_1") (pintype "passive"))
      (node (ref "U16") (pin "4") (pinfunction "C_4") (pintype "passive"))
    )
    (net (code "91") (name "/PSEG_6") (class "Default")
      (node (ref "F14") (pin "1") (pinfunction "1_1") (pintype "passive"))
      (node (ref "F6") (pin "2") (pinfunction "2_2") (pintype "passive"))
      (node (ref "Q2") (pin "3") (pinfunction "S_3") (pintype "passive"))
      (node (ref "R6") (pin "1") (pinfunction "1_1") (pintype "passive"))
      (node (ref "R84") (pin "1") (pinfunction "1_1") (pintype "passive"))
      (node (ref "U15") (pin "4") (pinfunction "C_4") (pintype "passive"))
    )
    (net (code "92") (name "/PSEG_7") (class "Default")
      (node (ref "F15") (pin "1") (pinfunction "1_1") (pintype "passive"))
      (node (ref "F7") (pin "2") (pinfunction "2_2") (pintype "passive"))
      (node (ref "Q1") (pin "3") (pinfunction "S_3") (pintype "passive"))
      (node (ref "R7") (pin "1") (pinfunction "1_1") (pintype "passive"))
      (node (ref "R85") (pin "1") (pinfunction "1_1") (pintype "passive"))
      (node (ref "U11") (pin "4") (pinfunction "C_4") (pintype "passive"))
    )
    (net (code "93") (name "/PSEG_8") (class "Default")
      (node (ref "F16") (pin "1") (pinfunction "1_1") (pintype "passive"))
      (node (ref "F8") (pin "2") (pinfunction "2_2") (pintype "passive"))
      (node (ref "Q10") (pin "2") (pinfunction "S_2") (pintype "passive"))
      (node (ref "R8") (pin "1") (pinfunction "1_1") (pintype "passive"))
      (node (ref "R96") (pin "1") (pinfunction "1_1") (pintype "passive"))
      (node (ref "U10") (pin "4") (pinfunction "C_4") (pintype "passive"))
    )
    (net (code "94") (name "/PTRACE1") (class "Default")
      (node (ref "F1") (pin "1") (pinfunction "1_1") (pintype "passive"))
      (node (ref "R24") (pin "1") (pinfunction "1_1") (pintype "passive"))
      (node (ref "R48") (pin "1") (pinfunction "1_1") (pintype "passive"))
    )
    (net (code "95") (name "/PTRACE2") (class "Default")
      (node (ref "F2") (pin "1") (pinfunction "1_1") (pintype "passive"))
      (node (ref "R23") (pin "1") (pinfunction "1_1") (pintype "passive"))
      (node (ref "R47") (pin "1") (pinfunction "1_1") (pintype "passive"))
    )
    (net (code "96") (name "/PTRACE3") (class "Default")
      (node (ref "F3") (pin "1") (pinfunction "1_1") (pintype "passive"))
      (node (ref "R22") (pin "1") (pinfunction "1_1") (pintype "passive"))
      (node (ref "R46") (pin "1") (pinfunction "1_1") (pintype "passive"))
    )
    (net (code "97") (name "/PTRACE4") (class "Default")
      (node (ref "F4") (pin "1") (pinfunction "1_1") (pintype "passive"))
      (node (ref "R21") (pin "1") (pinfunction "1_1") (pintype "passive"))
      (node (ref "R45") (pin "1") (pinfunction "1_1") (pintype "passive"))
    )
    (net (code "98") (name "/PTRACE5") (class "Default")
      (node (ref "F5") (pin "1") (pinfunction "1_1") (pintype "passive"))
      (node (ref "R20") (pin "1") (pinfunction "1_1") (pintype "passive"))
      (node (ref "R44") (pin "1") (pinfunction "1_1") (pintype "passive"))
    )
    (net (code "99") (name "/PTRACE6") (class "Default")
      (node (ref "F6") (pin "1") (pinfunction "1_1") (pintype "passive"))
      (node (ref "R19") (pin "1") (pinfunction "1_1") (pintype "passive"))
      (node (ref "R43") (pin "1") (pinfunction "1_1") (pintype "passive"))
    )
    (net (code "100") (name "/PTRACE7") (class "Default")
      (node (ref "F7") (pin "1") (pinfunction "1_1") (pintype "passive"))
      (node (ref "R18") (pin "1") (pinfunction "1_1") (pintype "passive"))
      (node (ref "R42") (pin "1") (pinfunction "1_1") (pintype "passive"))
    )
    (net (code "101") (name "/PTRACE8") (class "Default")
      (node (ref "F8") (pin "1") (pinfunction "1_1") (pintype "passive"))
      (node (ref "R17") (pin "1") (pinfunction "1_1") (pintype "passive"))
    )
    (net (code "102") (name "/P_Gate") (class "Default")
      (node (ref "Q10") (pin "1") (pinfunction "G_1") (pintype "passive"))
      (node (ref "R96") (pin "2") (pinfunction "2_2") (pintype "passive"))
      (node (ref "R97") (pin "2") (pinfunction "2_2") (pintype "passive"))
    )
    (net (code "103") (name "/RESET") (class "Default")
      (node (ref "C22") (pin "2") (pinfunction "2_2") (pintype "passive"))
      (node (ref "J1") (pin "5") (pinfunction "5_5") (pintype "passive"))
      (node (ref "R98") (pin "1") (pinfunction "1_1") (pintype "passive"))
      (node (ref "U1") (pin "31") (pinfunction "PE0_(RESET)_31") (pintype "input"))
    )
    (net (code "104") (name "/RX_CAN1") (class "Default")
      (node (ref "R66") (pin "2") (pinfunction "2_2") (pintype "passive"))
      (node (ref "U1") (pin "7") (pinfunction "PC3_(RXCAN)_7") (pintype "input"))
    )
    (net (code "105") (name "/RX_CAN2") (class "Default")
      (node (ref "R66") (pin "1") (pinfunction "1_1") (pintype "passive"))
      (node (ref "U5") (pin "2") (pinfunction "RX_CAN_2") (pintype "output"))
    )
    (net (code "106") (name "/SCK") (class "Default")
      (node (ref "J1") (pin "3") (pinfunction "3_3") (pintype "passive"))
      (node (ref "R80") (pin "1") (pinfunction "1_1") (pintype "passive"))
      (node (ref "U1") (pin "12") (pinfunction "PD4_(ADC1/RXLIN/SCK_A)_12") (pintype "bidirectional"))
    )
    (net (code "107") (name "/SEG_1") (class "Default")
      (node (ref "F9") (pin "2") (pinfunction "2_2") (pintype "passive"))
    )
    (net (code "108") (name "/SEG_2") (class "Default")
      (node (ref "F10") (pin "2") (pinfunction "2_2") (pintype "passive"))
    )
    (net (code "109") (name "/SEG_3") (class "Default")
      (node (ref "F11") (pin "2") (pinfunction "2_2") (pintype "passive"))
    )
    (net (code "110") (name "/SEG_4") (class "Default")
      (node (ref "F12") (pin "2") (pinfunction "2_2") (pintype "passive"))
    )
    (net (code "111") (name "/SEG_5") (class "Default")
      (node (ref "F13") (pin "2") (pinfunction "2_2") (pintype "passive"))
    )
    (net (code "112") (name "/SEG_6") (class "Default")
      (node (ref "F14") (pin "2") (pinfunction "2_2") (pintype "passive"))
    )
    (net (code "113") (name "/SEG_7") (class "Default")
      (node (ref "F15") (pin "2") (pinfunction "2_2") (pintype "passive"))
    )
    (net (code "114") (name "/SEG_8") (class "Default")
      (node (ref "F16") (pin "2") (pinfunction "2_2") (pintype "passive"))
    )
    (net (code "115") (name "/TH1") (class "Default")
      (node (ref "TH1") (pin "2") (pinfunction "2_2") (pintype "passive"))
      (node (ref "U20") (pin "1") (pinfunction "CH4_1") (pintype "input"))
    )
    (net (code "116") (name "/TH2") (class "Default")
      (node (ref "TH2") (pin "2") (pinfunction "2_2") (pintype "passive"))
      (node (ref "U20") (pin "2") (pinfunction "CH6_2") (pintype "input"))
    )
    (net (code "117") (name "/TH3") (class "Default")
      (node (ref "TH3") (pin "2") (pinfunction "2_2") (pintype "passive"))
      (node (ref "U20") (pin "4") (pinfunction "CH7_4") (pintype "input"))
    )
    (net (code "118") (name "/TH4") (class "Default")
      (node (ref "TH4") (pin "2") (pinfunction "2_2") (pintype "passive"))
      (node (ref "U20") (pin "5") (pinfunction "CH5_5") (pintype "input"))
    )
    (net (code "119") (name "/TH5") (class "Default")
      (node (ref "TH5") (pin "2") (pinfunction "2_2") (pintype "passive"))
      (node (ref "U20") (pin "12") (pinfunction "CH3_12") (pintype "input"))
    )
    (net (code "120") (name "/TH6") (class "Default")
      (node (ref "TH6") (pin "2") (pinfunction "2_2") (pintype "passive"))
      (node (ref "U20") (pin "13") (pinfunction "CH0_13") (pintype "input"))
    )
    (net (code "121") (name "/TH7") (class "Default")
      (node (ref "TH7") (pin "2") (pinfunction "2_2") (pintype "passive"))
      (node (ref "U20") (pin "14") (pinfunction "CH1_14") (pintype "input"))
    )
    (net (code "122") (name "/TH8") (class "Default")
      (node (ref "TH8") (pin "2") (pinfunction "2_2") (pintype "passive"))
      (node (ref "U20") (pin "15") (pinfunction "CH2_15") (pintype "input"))
    )
    (net (code "123") (name "/TX_CAN1") (class "Default")
      (node (ref "R65") (pin "2") (pinfunction "2_2") (pintype "passive"))
      (node (ref "U1") (pin "6") (pinfunction "PC2_(TXCAN)_6") (pintype "output"))
    )
    (net (code "124") (name "/TX_CAN2") (class "Default")
      (node (ref "R65") (pin "1") (pinfunction "1_1") (pintype "passive"))
      (node (ref "U5") (pin "3") (pinfunction "TX_CAN_3") (pintype "input"))
    )
    (net (code "125") (name "/VSENSE1") (class "Default")
      (node (ref "C8") (pin "2") (pinfunction "2_2") (pintype "passive"))
      (node (ref "R77") (pin "2") (pinfunction "2_2") (pintype "passive"))
      (node (ref "U1") (pin "28") (pinfunction "PD0_(ADC4)_28") (pintype "input"))
    )
    (net (code "126") (name "/VSENSE2") (class "Default")
      (node (ref "C7") (pin "2") (pinfunction "2_2") (pintype "passive"))
      (node (ref "R76") (pin "2") (pinfunction "2_2") (pintype "passive"))
      (node (ref "U1") (pin "27") (pinfunction "PB7_(ADC7)_27") (pintype "input"))
    )
    (net (code "127") (name "/VSENSE3") (class "Default")
      (node (ref "C6") (pin "2") (pinfunction "2_2") (pintype "passive"))
      (node (ref "R75") (pin "2") (pinfunction "2_2") (pintype "passive"))
      (node (ref "U1") (pin "14") (pinfunction "PD6_(ADC3/INT0)_14") (pintype "input"))
    )
    (net (code "128") (name "/VSENSE4") (class "Default")
      (node (ref "C5") (pin "2") (pinfunction "2_2") (pintype "passive"))
      (node (ref "R74") (pin "2") (pinfunction "2_2") (pintype "passive"))
      (node (ref "U1") (pin "16") (pinfunction "PB2_(ADC5)_16") (pintype "input"))
    )
    (net (code "129") (name "/VSENSE5") (class "Default")
      (node (ref "C4") (pin "2") (pinfunction "2_2") (pintype "passive"))
      (node (ref "R73") (pin "2") (pinfunction "2_2") (pintype "passive"))
      (node (ref "U1") (pin "17") (pinfunction "PC4_(ADC8)_17") (pintype "input"))
    )
    (net (code "130") (name "/VSENSE6") (class "Default")
      (node (ref "C3") (pin "2") (pinfunction "2_2") (pintype "passive"))
      (node (ref "R72") (pin "2") (pinfunction "2_2") (pintype "passive"))
      (node (ref "U1") (pin "18") (pinfunction "PC5_(ADC9)_18") (pintype "input"))
    )
    (net (code "131") (name "/VSENSE7") (class "Default")
      (node (ref "C2") (pin "2") (pinfunction "2_2") (pintype "passive"))
      (node (ref "R71") (pin "2") (pinfunction "2_2") (pintype "passive"))
      (node (ref "U1") (pin "26") (pinfunction "PB5_(ADC6)_26") (pintype "input"))
    )
    (net (code "132") (name "/VSENSE8") (class "Default")
      (node (ref "C1") (pin "2") (pinfunction "2_2") (pintype "passive"))
      (node (ref "R70") (pin "2") (pinfunction "2_2") (pintype "passive"))
      (node (ref "U1") (pin "22") (pinfunction "PC6_(_ADC10)_22") (pintype "input"))
    )
    (net (code "133") (name "/WAKE_IN_GLV1") (class "Default")
      (node (ref "J2") (pin "6") (pinfunction "6_6") (pintype "passive"))
      (node (ref "J3") (pin "6") (pinfunction "6_6") (pintype "passive"))
      (node (ref "U14") (pin "1") (pinfunction "A_1") (pintype "passive"))
    )
    (net (code "134") (name "/WAKE_IN_GLV2") (class "Default")
      (node (ref "R63") (pin "1") (pinfunction "1_1") (pintype "passive"))
      (node (ref "U14") (pin "2") (pinfunction "K_2") (pintype "passive"))
    )
    (net (code "135") (name "/WAKE_IN_HV1") (class "Default")
      (node (ref "D1") (pin "1") (pinfunction "A_1") (pintype "passive"))
      (node (ref "R64") (pin "2") (pinfunction "2_2") (pintype "passive"))
      (node (ref "R95b") (pin "1") (pinfunction "1_1") (pintype "passive"))
      (node (ref "U1") (pin "30") (pinfunction "PC0(INT3)_30") (pintype "passive"))
    )
    (net (code "136") (name "/WAKE_IN_HV2") (class "Default")
      (node (ref "R64") (pin "1") (pinfunction "1_1") (pintype "passive"))
      (node (ref "R88") (pin "2") (pinfunction "2_2") (pintype "passive"))
      (node (ref "U14") (pin "3") (pinfunction "E_3") (pintype "passive"))
    )
    (net (code "137") (name "/WAKE_OUT_GLV1") (class "Default")
      (node (ref "R78") (pin "1") (pinfunction "1_1") (pintype "passive"))
      (node (ref "U13") (pin "3") (pinfunction "E_3") (pintype "passive"))
    )
    (net (code "138") (name "/WAKE_OUT_GLV2") (class "Default")
      (node (ref "J2") (pin "3") (pinfunction "3_3") (pintype "passive"))
      (node (ref "J3") (pin "3") (pinfunction "3_3") (pintype "passive"))
      (node (ref "R78") (pin "2") (pinfunction "2_2") (pintype "passive"))
    )
    (net (code "139") (name "/WAKE_OUT_HV1") (class "Default")
      (node (ref "U1") (pin "29") (pinfunction "PD0_(PSCOUT0A)_29") (pintype "output"))
      (node (ref "U13") (pin "1") (pinfunction "A_1") (pintype "passive"))
    )
    (net (code "140") (name "/WAKE_OUT_HV2") (class "Default")
      (node (ref "R69") (pin "2") (pinfunction "2_2") (pintype "passive"))
      (node (ref "U13") (pin "2") (pinfunction "K_2") (pintype "passive"))
    )
    (net (code "141") (name "/XTAL1") (class "Default")
      (node (ref "C9") (pin "2") (pinfunction "2_2") (pintype "passive"))
      (node (ref "U1") (pin "10") (pinfunction "PE1_(XTAL1)_10") (pintype "input"))
      (node (ref "Y1") (pin "1") (pinfunction "OSC1_1") (pintype "passive"))
    )
    (net (code "142") (name "/XTAL2") (class "Default")
      (node (ref "C10") (pin "2") (pinfunction "2_2") (pintype "passive"))
      (node (ref "U1") (pin "11") (pinfunction "PE2_(XTAL2)_11") (pintype "input"))
      (node (ref "Y1") (pin "2") (pinfunction "OSC2_2") (pintype "passive"))
    )
    (net (code "143") (name "5V_HV") (class "Default")
      (node (ref "C11") (pin "2") (pinfunction "2_2") (pintype "passive"))
      (node (ref "C12") (pin "2") (pinfunction "2_2") (pintype "passive"))
      (node (ref "C13") (pin "2") (pinfunction "2_2") (pintype "passive"))
      (node (ref "C16") (pin "2") (pinfunction "2_2") (pintype "passive"))
      (node (ref "C21") (pin "2") (pinfunction "2_2") (pintype "passive"))
      (node (ref "C38") (pin "1") (pinfunction "1_1") (pintype "passive"))
      (node (ref "C41") (pin "1") (pinfunction "1_1") (pintype "passive"))
      (node (ref "D2") (pin "1") (pinfunction "A_1") (pintype "passive"))
      (node (ref "J1") (pin "2") (pinfunction "2_2") (pintype "passive"))
      (node (ref "L1") (pin "1") (pinfunction "1_1") (pintype "passive"))
      (node (ref "R68") (pin "2") (pinfunction "2_2") (pintype "passive"))
      (node (ref "R95a") (pin "1") (pinfunction "1_1") (pintype "passive"))
      (node (ref "R98") (pin "2") (pinfunction "2_2") (pintype "passive"))
      (node (ref "U1") (pin "4") (pinfunction "VCC_4") (pintype "power_in"))
      (node (ref "U14") (pin "4") (pinfunction "C_4") (pintype "passive"))
      (node (ref "U20") (pin "16") (pinfunction "VDD_16") (pintype "power_in"))
      (node (ref "U5") (pin "1") (pinfunction "VCC1_1") (pintype "power_in"))
      (node (ref "VR1") (pin "5") (pinfunction "OUT_5") (pintype "passive"))
    )
    (net (code "144") (name "Amp_Pwr") (class "Default")
      (node (ref "C50") (pin "2") (pinfunction "2_2") (pintype "passive"))
      (node (ref "C52") (pin "2") (pinfunction "2_2") (pintype "passive"))
      (node (ref "Q10") (pin "3") (pinfunction "D_3") (pintype "passive"))
      (node (ref "U6") (pin "4") (pinfunction "V+_4") (pintype "power_in"))
      (node (ref "U7") (pin "4") (pinfunction "V+_4") (pintype "power_in"))
    )
    (net (code "145") (name "GND_CELL") (class "Default")
      (node (ref "C1") (pin "1") (pinfunction "1_1") (pintype "passive"))
      (node (ref "C10") (pin "1") (pinfunction "1_1") (pintype "passive"))
      (node (ref "C11") (pin "1") (pinfunction "1_1") (pintype "passive"))
      (node (ref "C12") (pin "1") (pinfunction "1_1") (pintype "passive"))
      (node (ref "C13") (pin "1") (pinfunction "1_1") (pintype "passive"))
      (node (ref "C16") (pin "1") (pinfunction "1_1") (pintype "passive"))
      (node (ref "C2") (pin "1") (pinfunction "1_1") (pintype "passive"))
      (node (ref "C20") (pin "1") (pinfunction "1_1") (pintype "passive"))
      (node (ref "C21") (pin "1") (pinfunction "1_1") (pintype "passive"))
      (node (ref "C22") (pin "1") (pinfunction "1_1") (pintype "passive"))
      (node (ref "C3") (pin "1") (pinfunction "1_1") (pintype "passive"))
      (node (ref "C38") (pin "2") (pinfunction "2_2") (pintype "passive"))
      (node (ref "C39") (pin "2") (pinfunction "2_2") (pintype "passive"))
      (node (ref "C4") (pin "1") (pinfunction "1_1") (pintype "passive"))
      (node (ref "C40") (pin "2") (pinfunction "2_2") (pintype "passive"))
      (node (ref "C41") (pin "2") (pinfunction "2_2") (pintype "passive"))
      (node (ref "C50") (pin "1") (pinfunction "1_1") (pintype "passive"))
      (node (ref "C6") (pin "1") (pinfunction "1_1") (pintype "passive"))
      (node (ref "C7") (pin "1") (pinfunction "1_1") (pintype "passive"))
      (node (ref "C8") (pin "1") (pinfunction "1_1") (pintype "passive"))
      (node (ref "C9") (pin "1") (pinfunction "1_1") (pintype "passive"))
      (node (ref "C99") (pin "1") (pinfunction "1_1") (pintype "passive"))
      (node (ref "J1") (pin "6") (pinfunction "6_6") (pintype "passive"))
      (node (ref "Q8") (pin "3") (pinfunction "S_3") (pintype "passive"))
      (node (ref "Q9") (pin "2") (pinfunction "S_2") (pintype "passive"))
      (node (ref "R10") (pin "1") (pinfunction "1_1") (pintype "passive"))
      (node (ref "R11") (pin "1") (pinfunction "1_1") (pintype "passive"))
      (node (ref "R12") (pin "1") (pinfunction "1_1") (pintype "passive"))
      (node (ref "R13") (pin "1") (pinfunction "1_1") (pintype "passive"))
      (node (ref "R14") (pin "1") (pinfunction "1_1") (pintype "passive"))
      (node (ref "R15") (pin "1") (pinfunction "1_1") (pintype "passive"))
      (node (ref "R16") (pin "1") (pinfunction "1_1") (pintype "passive"))
      (node (ref "R25") (pin "2") (pinfunction "2_2") (pintype "passive"))
      (node (ref "R26") (pin "2") (pinfunction "2_2") (pintype "passive"))
      (node (ref "R27") (pin "2") (pinfunction "2_2") (pintype "passive"))
      (node (ref "R28") (pin "2") (pinfunction "2_2") (pintype "passive"))
      (node (ref "R29") (pin "2") (pinfunction "2_2") (pintype "passive"))
      (node (ref "R30") (pin "2") (pinfunction "2_2") (pintype "passive"))
      (node (ref "R31") (pin "2") (pinfunction "2_2") (pintype "passive"))
      (node (ref "R41") (pin "1") (pinfunction "1_1") (pintype "passive"))
      (node (ref "R50") (pin "1") (pinfunction "1_1") (pintype "passive"))
      (node (ref "R62") (pin "2") (pinfunction "2_2") (pintype "passive"))
      (node (ref "R69") (pin "1") (pinfunction "1_1") (pintype "passive"))
      (node (ref "R88") (pin "1") (pinfunction "1_1") (pintype "passive"))
      (node (ref "R89") (pin "2") (pinfunction "2_2") (pintype "passive"))
      (node (ref "R9") (pin "1") (pinfunction "1_1") (pintype "passive"))
      (node (ref "R90") (pin "1") (pinfunction "1_1") (pintype "passive"))
      (node (ref "R91") (pin "2") (pinfunction "2_2") (pintype "passive"))
      (node (ref "R99") (pin "1") (pinfunction "1_1") (pintype "passive"))
      (node (ref "TH1") (pin "1") (pinfunction "1_1") (pintype "passive"))
      (node (ref "TH2") (pin "1") (pinfunction "1_1") (pintype "passive"))
      (node (ref "TH3") (pin "1") (pinfunction "1_1") (pintype "passive"))
      (node (ref "TH4") (pin "1") (pinfunction "1_1") (pintype "passive"))
      (node (ref "TH5") (pin "1") (pinfunction "1_1") (pintype "passive"))
      (node (ref "TH6") (pin "1") (pinfunction "1_1") (pintype "passive"))
      (node (ref "TH7") (pin "1") (pinfunction "1_1") (pintype "passive"))
      (node (ref "TH8") (pin "1") (pinfunction "1_1") (pintype "passive"))
      (node (ref "U1") (pin "5") (pinfunction "GND_5") (pintype "power_in"))
      (node (ref "U20") (pin "7") (pinfunction "VEE_7") (pintype "power_in"))
      (node (ref "U20") (pin "8") (pinfunction "VSS_8") (pintype "power_in"))
      (node (ref "U5") (pin "4") (pinfunction "GND1_4") (pintype "power_in"))
      (node (ref "U6") (pin "11") (pinfunction "V-_11") (pintype "power_in"))
      (node (ref "U7") (pin "11") (pinfunction "V-_11") (pintype "power_in"))
      (node (ref "VR1") (pin "3") (pinfunction "GND_3") (pintype "passive"))
    )
    (net (code "146") (name "GND_GLV") (class "Default")
      (node (ref "C14") (pin "1") (pinfunction "1_1") (pintype "passive"))
      (node (ref "C15") (pin "2") (pinfunction "2_2") (pintype "passive"))
      (node (ref "C17") (pin "1") (pinfunction "1_1") (pintype "passive"))
      (node (ref "J2") (pin "1") (pinfunction "1_1") (pintype "passive"))
      (node (ref "J3") (pin "1") (pinfunction "1_1") (pintype "passive"))
      (node (ref "R61") (pin "2") (pinfunction "2_2") (pintype "passive"))
      (node (ref "R63") (pin "2") (pinfunction "2_2") (pintype "passive"))
      (node (ref "U5") (pin "5") (pinfunction "GND2_5") (pintype "power_in"))
      (node (ref "VR2") (pin "4") (pinfunction "GND_4") (pintype "power_in"))
    )
    (net (code "147") (name "Net-(C5-Pad1)") (class "Default")
      (node (ref "C5") (pin "1") (pinfunction "1_1") (pintype "passive"))
      (node (ref "C52") (pin "1") (pinfunction "1_1") (pintype "passive"))
    )
    (net (code "148") (name "heat1") (class "Default")
      (node (ref "R1") (pin "2") (pinfunction "Heat_2") (pintype "passive"))
      (node (ref "R2") (pin "2") (pinfunction "Heat_2") (pintype "passive"))
      (node (ref "R3") (pin "2") (pinfunction "Heat_2") (pintype "passive"))
      (node (ref "R4") (pin "2") (pinfunction "Heat_2") (pintype "passive"))
    )
    (net (code "149") (name "heat2") (class "Default")
      (node (ref "R5") (pin "2") (pinfunction "Heat_2") (pintype "passive"))
      (node (ref "R6") (pin "2") (pinfunction "Heat_2") (pintype "passive"))
      (node (ref "R7") (pin "2") (pinfunction "Heat_2") (pintype "passive"))
      (node (ref "R8") (pin "2") (pinfunction "Heat_2") (pintype "passive"))
    )
    (net (code "150") (name "unconnected-(VR1-NC-Pad4)") (class "Default")
      (node (ref "VR1") (pin "4") (pinfunction "NC_4") (pintype "passive"))
    )
  )
)
